# CAN_Test_Runner.net
KiCad netlist of a schematic drawn in Altium Designer
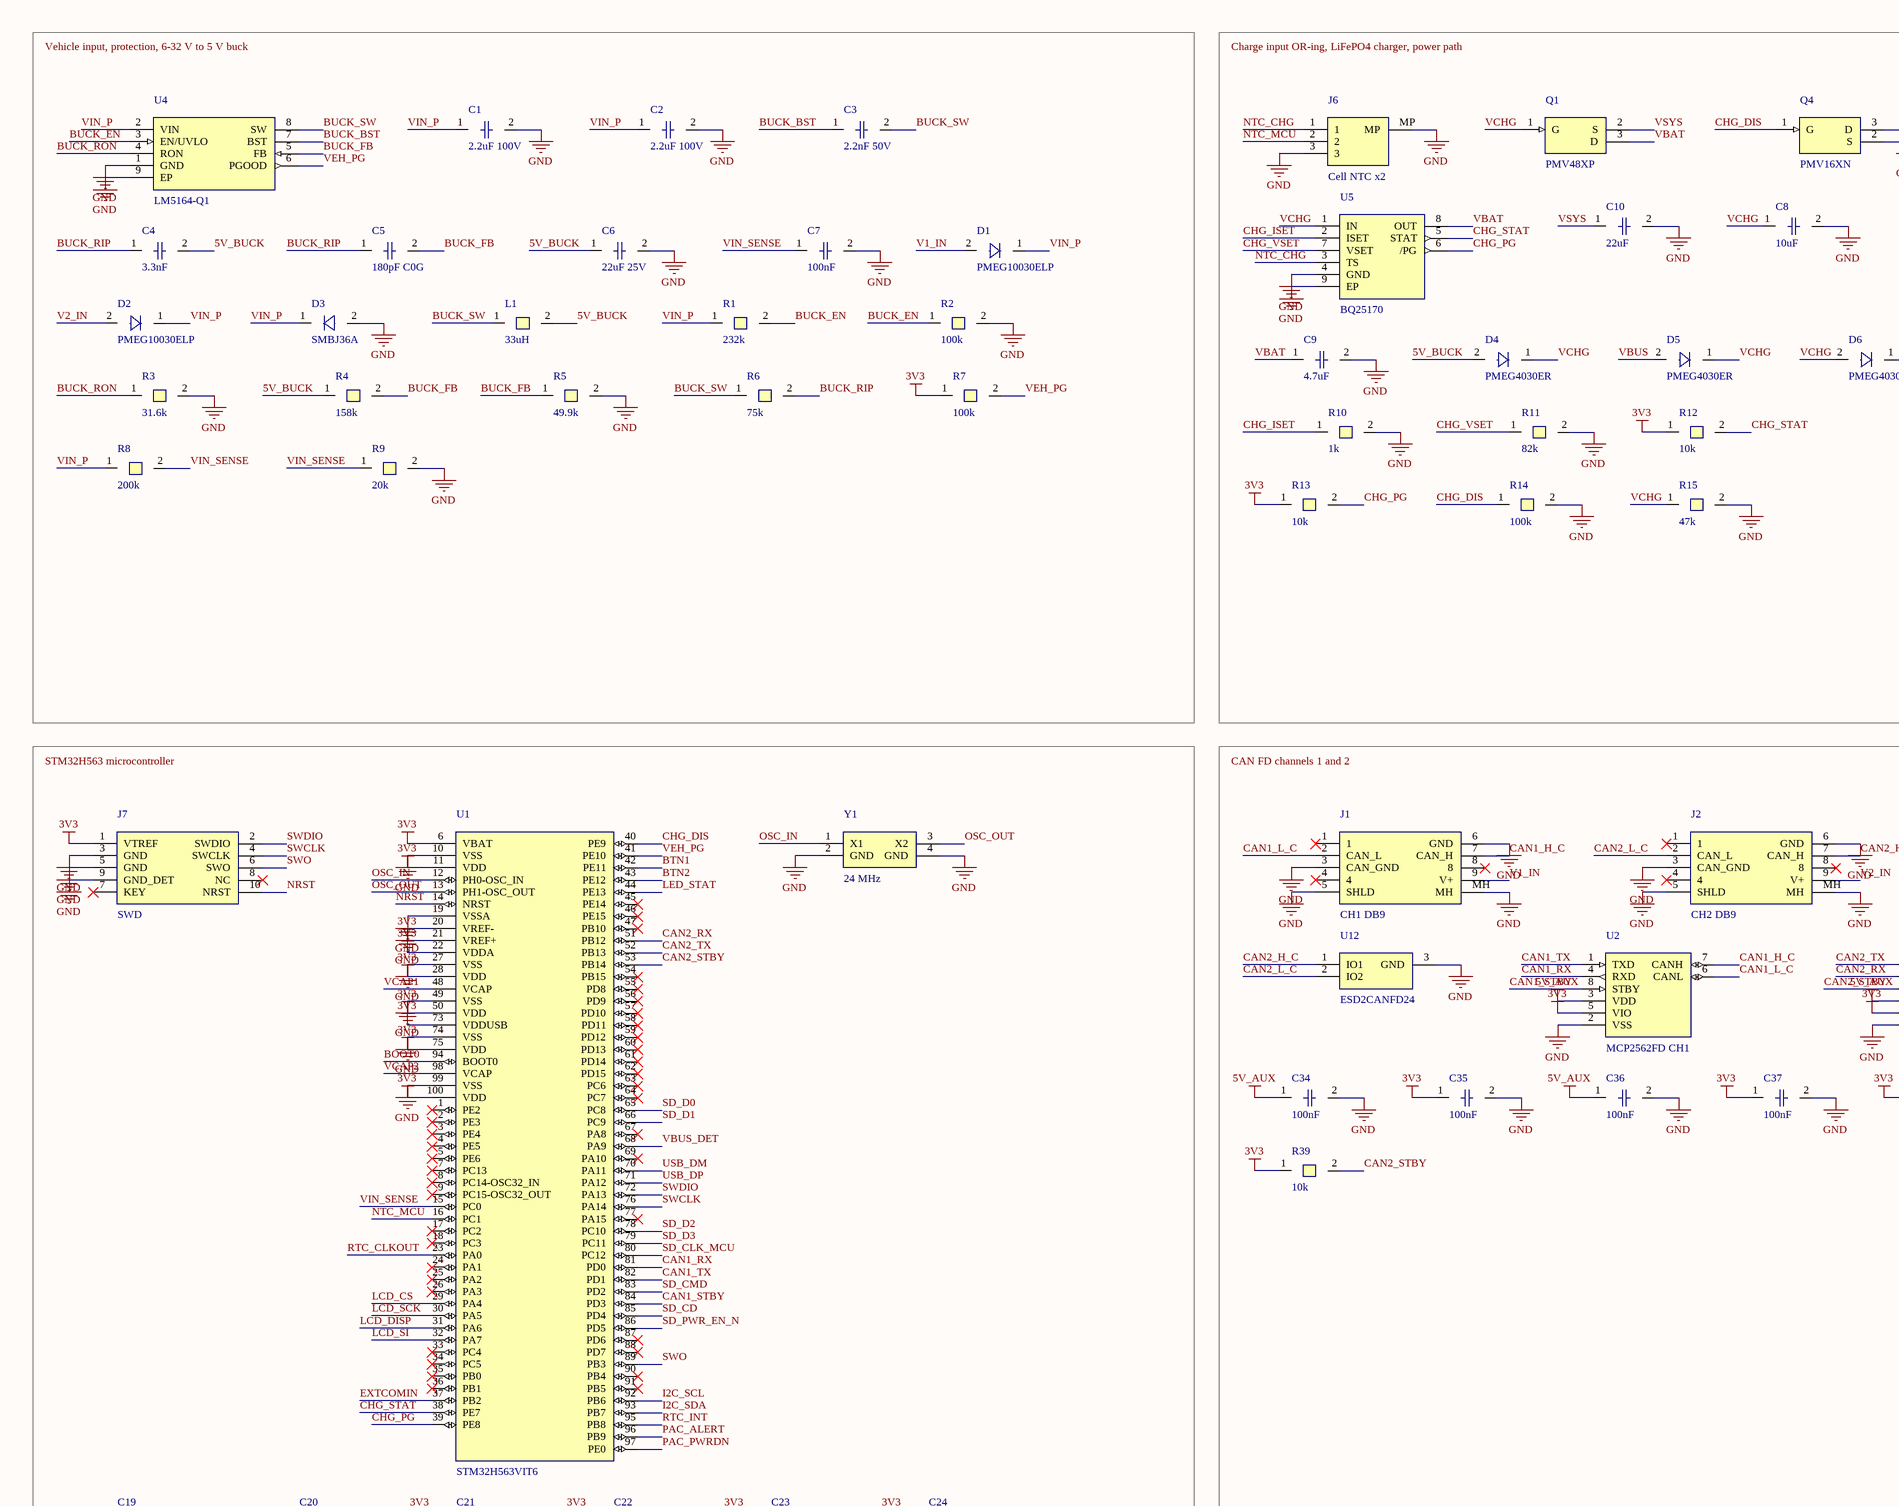
[diagram p0: CAN_Test_Runner.SchDoc, top left]
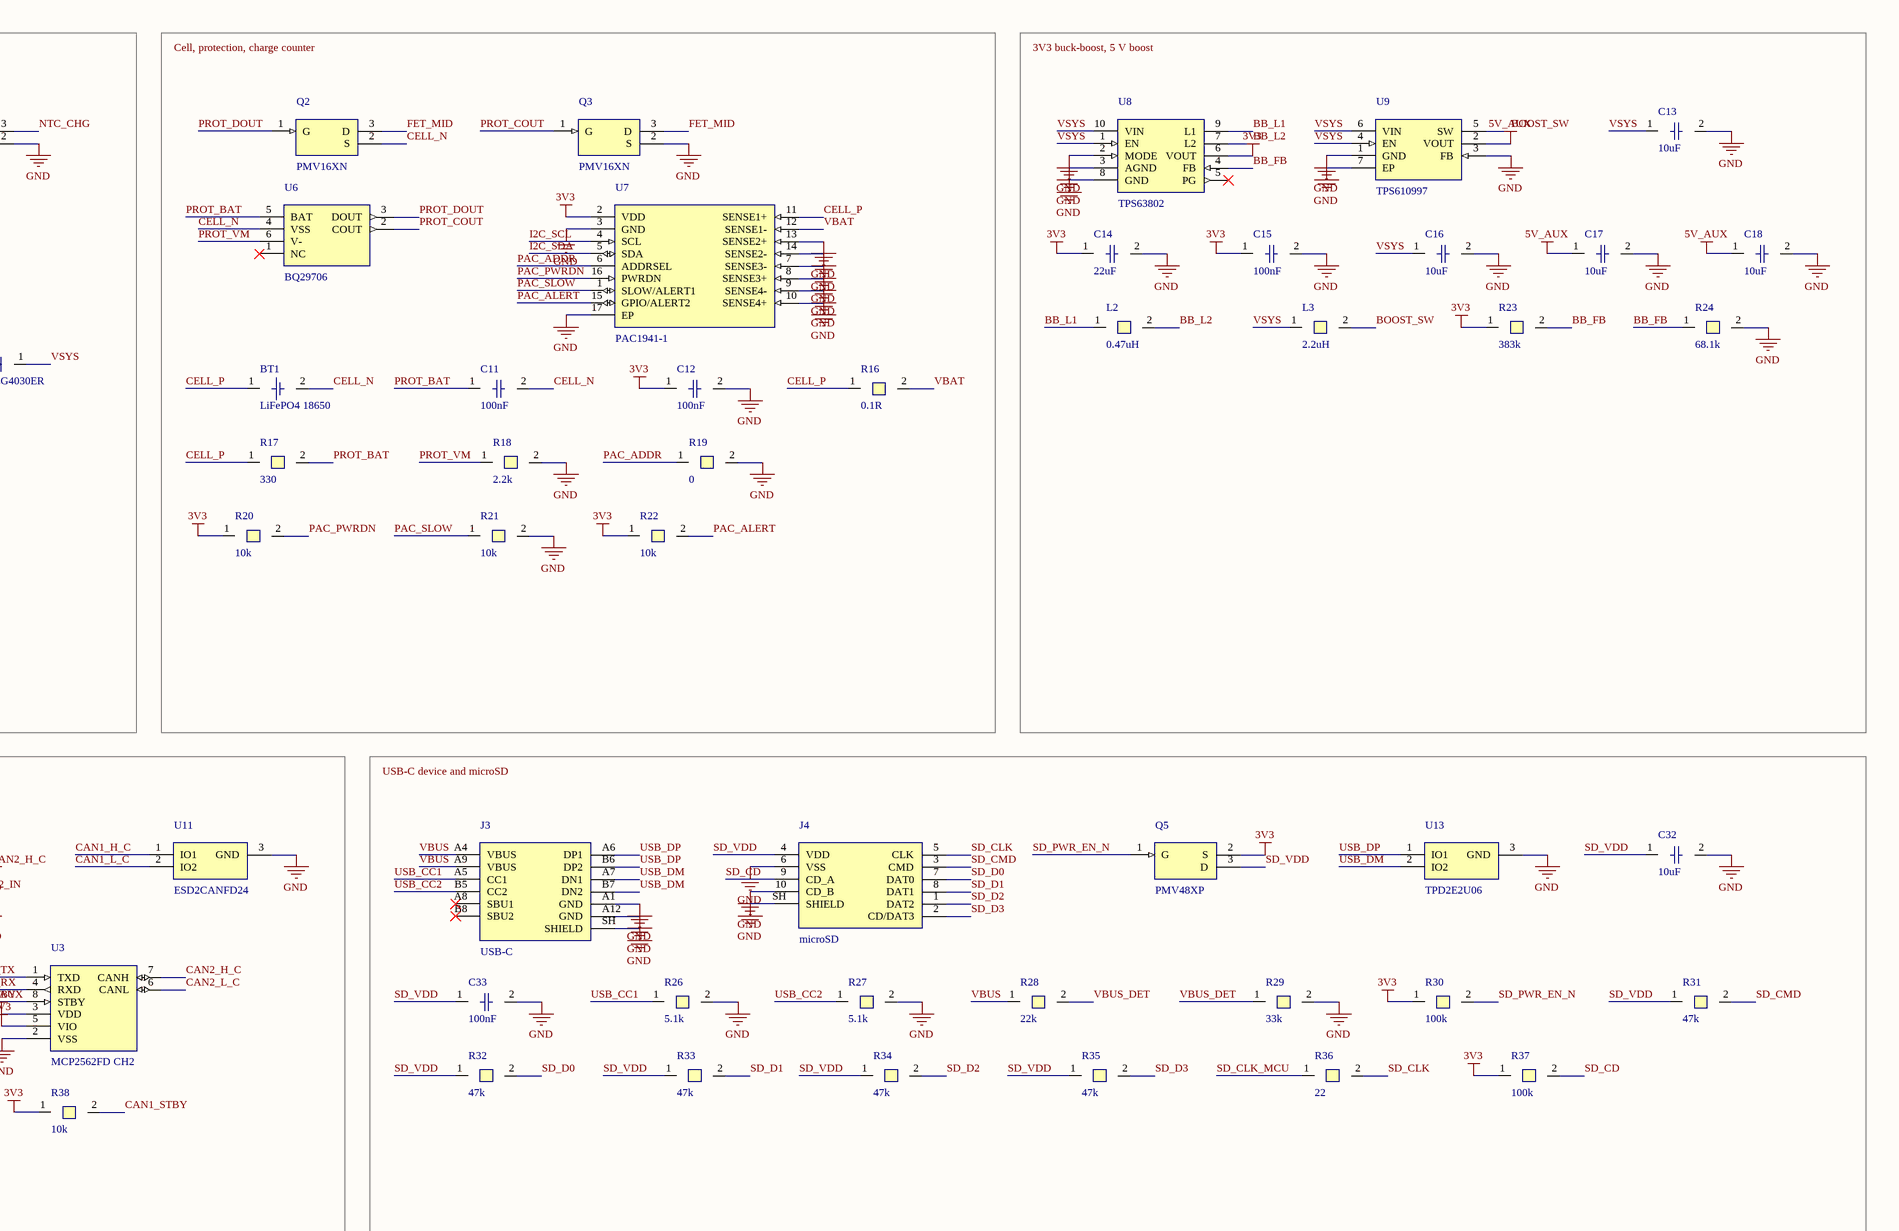
[diagram p1: CAN_Test_Runner.SchDoc, top right]
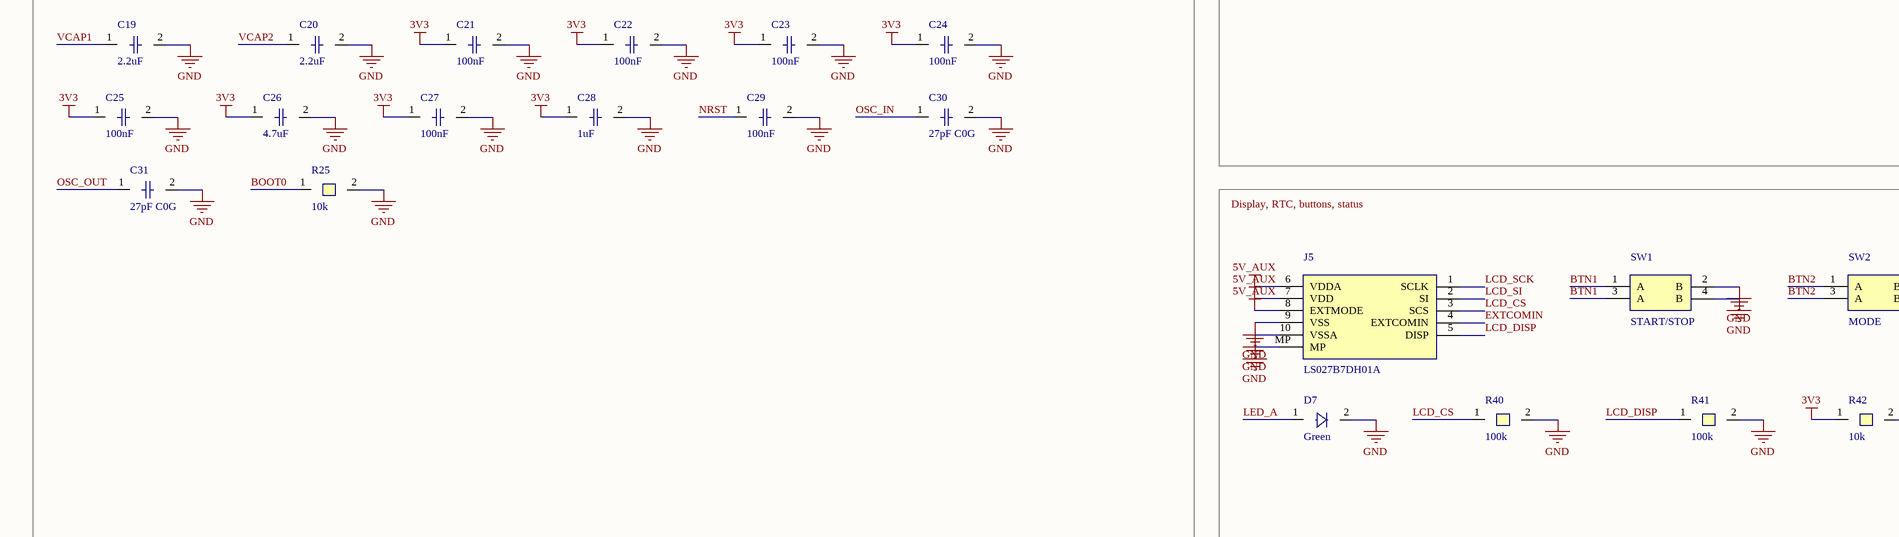
[diagram p2: CAN_Test_Runner.SchDoc, bottom left]
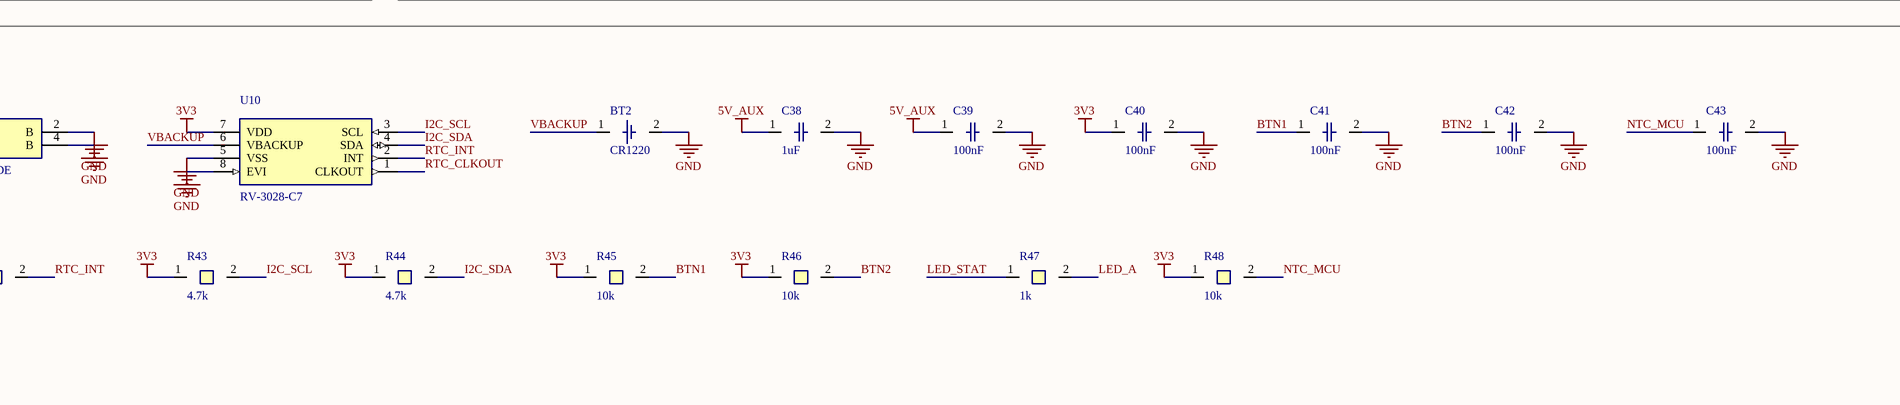
[diagram p3: CAN_Test_Runner.SchDoc, bottom right]

(export (version "E")
  (design (tool "Eeschema 10.0.6"))
  (components
    (comp (ref "BT1")
      (value "LiFePO4 18650")
      (footprint "BATT_KEYSTONE_1042_18650")
      (description "18650 cell holder")
      (fields (field (name "MPN") "Keystone 1042"))
      (libsource (lib "*") (part "BATT_18650"))
    )
    (comp (ref "BT2")
      (value "CR1220")
      (footprint "BATT_KEYSTONE_3000_12MM")
      (description "Coin cell retainer")
      (fields (field (name "MPN") "Keystone 3000"))
      (libsource (lib "*") (part "BATT_COIN"))
    )
    (comp (ref "C1")
      (value "2.2uF 100V")
      (footprint "C1210")
      (description "Capacitor, non-polarised")
      (fields (field (name "MPN") "generic 1210 X7R/C0G"))
      (libsource (lib "*") (part "CAP"))
    )
    (comp (ref "C2")
      (value "2.2uF 100V")
      (footprint "C1210")
      (description "Capacitor, non-polarised")
      (fields (field (name "MPN") "generic 1210 X7R/C0G"))
      (libsource (lib "*") (part "CAP"))
    )
    (comp (ref "C3")
      (value "2.2nF 50V")
      (footprint "C0603")
      (description "Capacitor, non-polarised")
      (fields (field (name "MPN") "generic 0603 X7R/C0G"))
      (libsource (lib "*") (part "CAP"))
    )
    (comp (ref "C4")
      (value "3.3nF")
      (footprint "C0603")
      (description "Capacitor, non-polarised")
      (fields (field (name "MPN") "generic 0603 X7R/C0G"))
      (libsource (lib "*") (part "CAP"))
    )
    (comp (ref "C5")
      (value "180pF C0G")
      (footprint "C0603")
      (description "Capacitor, non-polarised")
      (fields (field (name "MPN") "generic 0603 X7R/C0G"))
      (libsource (lib "*") (part "CAP"))
    )
    (comp (ref "C6")
      (value "22uF 25V")
      (footprint "C1210")
      (description "Capacitor, non-polarised")
      (fields (field (name "MPN") "generic 1210 X7R/C0G"))
      (libsource (lib "*") (part "CAP"))
    )
    (comp (ref "C7")
      (value "100nF")
      (footprint "C0603")
      (description "Capacitor, non-polarised")
      (fields (field (name "MPN") "generic 0603 X7R/C0G"))
      (libsource (lib "*") (part "CAP"))
    )
    (comp (ref "C8")
      (value "10uF")
      (footprint "C0805")
      (description "Capacitor, non-polarised")
      (fields (field (name "MPN") "generic 0805 X7R/C0G"))
      (libsource (lib "*") (part "CAP"))
    )
    (comp (ref "C9")
      (value "4.7uF")
      (footprint "C0805")
      (description "Capacitor, non-polarised")
      (fields (field (name "MPN") "generic 0805 X7R/C0G"))
      (libsource (lib "*") (part "CAP"))
    )
    (comp (ref "C10")
      (value "22uF")
      (footprint "C1210")
      (description "Capacitor, non-polarised")
      (fields (field (name "MPN") "generic 1210 X7R/C0G"))
      (libsource (lib "*") (part "CAP"))
    )
    (comp (ref "C11")
      (value "100nF")
      (footprint "C0603")
      (description "Capacitor, non-polarised")
      (fields (field (name "MPN") "generic 0603 X7R/C0G"))
      (libsource (lib "*") (part "CAP"))
    )
    (comp (ref "C12")
      (value "100nF")
      (footprint "C0603")
      (description "Capacitor, non-polarised")
      (fields (field (name "MPN") "generic 0603 X7R/C0G"))
      (libsource (lib "*") (part "CAP"))
    )
    (comp (ref "C13")
      (value "10uF")
      (footprint "C0805")
      (description "Capacitor, non-polarised")
      (fields (field (name "MPN") "generic 0805 X7R/C0G"))
      (libsource (lib "*") (part "CAP"))
    )
    (comp (ref "C14")
      (value "22uF")
      (footprint "C0805")
      (description "Capacitor, non-polarised")
      (fields (field (name "MPN") "generic 0805 X7R/C0G"))
      (libsource (lib "*") (part "CAP"))
    )
    (comp (ref "C15")
      (value "100nF")
      (footprint "C0603")
      (description "Capacitor, non-polarised")
      (fields (field (name "MPN") "generic 0603 X7R/C0G"))
      (libsource (lib "*") (part "CAP"))
    )
    (comp (ref "C16")
      (value "10uF")
      (footprint "C0805")
      (description "Capacitor, non-polarised")
      (fields (field (name "MPN") "generic 0805 X7R/C0G"))
      (libsource (lib "*") (part "CAP"))
    )
    (comp (ref "C17")
      (value "10uF")
      (footprint "C0805")
      (description "Capacitor, non-polarised")
      (fields (field (name "MPN") "generic 0805 X7R/C0G"))
      (libsource (lib "*") (part "CAP"))
    )
    (comp (ref "C18")
      (value "10uF")
      (footprint "C0805")
      (description "Capacitor, non-polarised")
      (fields (field (name "MPN") "generic 0805 X7R/C0G"))
      (libsource (lib "*") (part "CAP"))
    )
    (comp (ref "C19")
      (value "2.2uF")
      (footprint "C0603")
      (description "Capacitor, non-polarised")
      (fields (field (name "MPN") "generic 0603 X7R/C0G"))
      (libsource (lib "*") (part "CAP"))
    )
    (comp (ref "C20")
      (value "2.2uF")
      (footprint "C0603")
      (description "Capacitor, non-polarised")
      (fields (field (name "MPN") "generic 0603 X7R/C0G"))
      (libsource (lib "*") (part "CAP"))
    )
    (comp (ref "C21")
      (value "100nF")
      (footprint "C0603")
      (description "Capacitor, non-polarised")
      (fields (field (name "MPN") "generic 0603 X7R/C0G"))
      (libsource (lib "*") (part "CAP"))
    )
    (comp (ref "C22")
      (value "100nF")
      (footprint "C0603")
      (description "Capacitor, non-polarised")
      (fields (field (name "MPN") "generic 0603 X7R/C0G"))
      (libsource (lib "*") (part "CAP"))
    )
    (comp (ref "C23")
      (value "100nF")
      (footprint "C0603")
      (description "Capacitor, non-polarised")
      (fields (field (name "MPN") "generic 0603 X7R/C0G"))
      (libsource (lib "*") (part "CAP"))
    )
    (comp (ref "C24")
      (value "100nF")
      (footprint "C0603")
      (description "Capacitor, non-polarised")
      (fields (field (name "MPN") "generic 0603 X7R/C0G"))
      (libsource (lib "*") (part "CAP"))
    )
    (comp (ref "C25")
      (value "100nF")
      (footprint "C0603")
      (description "Capacitor, non-polarised")
      (fields (field (name "MPN") "generic 0603 X7R/C0G"))
      (libsource (lib "*") (part "CAP"))
    )
    (comp (ref "C26")
      (value "4.7uF")
      (footprint "C0805")
      (description "Capacitor, non-polarised")
      (fields (field (name "MPN") "generic 0805 X7R/C0G"))
      (libsource (lib "*") (part "CAP"))
    )
    (comp (ref "C27")
      (value "100nF")
      (footprint "C0603")
      (description "Capacitor, non-polarised")
      (fields (field (name "MPN") "generic 0603 X7R/C0G"))
      (libsource (lib "*") (part "CAP"))
    )
    (comp (ref "C28")
      (value "1uF")
      (footprint "C0603")
      (description "Capacitor, non-polarised")
      (fields (field (name "MPN") "generic 0603 X7R/C0G"))
      (libsource (lib "*") (part "CAP"))
    )
    (comp (ref "C29")
      (value "100nF")
      (footprint "C0603")
      (description "Capacitor, non-polarised")
      (fields (field (name "MPN") "generic 0603 X7R/C0G"))
      (libsource (lib "*") (part "CAP"))
    )
    (comp (ref "C30")
      (value "27pF C0G")
      (footprint "C0603")
      (description "Capacitor, non-polarised")
      (fields (field (name "MPN") "generic 0603 X7R/C0G"))
      (libsource (lib "*") (part "CAP"))
    )
    (comp (ref "C31")
      (value "27pF C0G")
      (footprint "C0603")
      (description "Capacitor, non-polarised")
      (fields (field (name "MPN") "generic 0603 X7R/C0G"))
      (libsource (lib "*") (part "CAP"))
    )
    (comp (ref "C32")
      (value "10uF")
      (footprint "C0805")
      (description "Capacitor, non-polarised")
      (fields (field (name "MPN") "generic 0805 X7R/C0G"))
      (libsource (lib "*") (part "CAP"))
    )
    (comp (ref "C33")
      (value "100nF")
      (footprint "C0603")
      (description "Capacitor, non-polarised")
      (fields (field (name "MPN") "generic 0603 X7R/C0G"))
      (libsource (lib "*") (part "CAP"))
    )
    (comp (ref "C34")
      (value "100nF")
      (footprint "C0603")
      (description "Capacitor, non-polarised")
      (fields (field (name "MPN") "generic 0603 X7R/C0G"))
      (libsource (lib "*") (part "CAP"))
    )
    (comp (ref "C35")
      (value "100nF")
      (footprint "C0603")
      (description "Capacitor, non-polarised")
      (fields (field (name "MPN") "generic 0603 X7R/C0G"))
      (libsource (lib "*") (part "CAP"))
    )
    (comp (ref "C36")
      (value "100nF")
      (footprint "C0603")
      (description "Capacitor, non-polarised")
      (fields (field (name "MPN") "generic 0603 X7R/C0G"))
      (libsource (lib "*") (part "CAP"))
    )
    (comp (ref "C37")
      (value "100nF")
      (footprint "C0603")
      (description "Capacitor, non-polarised")
      (fields (field (name "MPN") "generic 0603 X7R/C0G"))
      (libsource (lib "*") (part "CAP"))
    )
    (comp (ref "C38")
      (value "1uF")
      (footprint "C0603")
      (description "Capacitor, non-polarised")
      (fields (field (name "MPN") "generic 0603 X7R/C0G"))
      (libsource (lib "*") (part "CAP"))
    )
    (comp (ref "C39")
      (value "100nF")
      (footprint "C0603")
      (description "Capacitor, non-polarised")
      (fields (field (name "MPN") "generic 0603 X7R/C0G"))
      (libsource (lib "*") (part "CAP"))
    )
    (comp (ref "C40")
      (value "100nF")
      (footprint "C0603")
      (description "Capacitor, non-polarised")
      (fields (field (name "MPN") "generic 0603 X7R/C0G"))
      (libsource (lib "*") (part "CAP"))
    )
    (comp (ref "C41")
      (value "100nF")
      (footprint "C0603")
      (description "Capacitor, non-polarised")
      (fields (field (name "MPN") "generic 0603 X7R/C0G"))
      (libsource (lib "*") (part "CAP"))
    )
    (comp (ref "C42")
      (value "100nF")
      (footprint "C0603")
      (description "Capacitor, non-polarised")
      (fields (field (name "MPN") "generic 0603 X7R/C0G"))
      (libsource (lib "*") (part "CAP"))
    )
    (comp (ref "C43")
      (value "100nF")
      (footprint "C0603")
      (description "Capacitor, non-polarised")
      (fields (field (name "MPN") "generic 0603 X7R/C0G"))
      (libsource (lib "*") (part "CAP"))
    )
    (comp (ref "D1")
      (value "PMEG10030ELP")
      (footprint "SOD128")
      (description "Schottky diode (pad 1 = cathode)")
      (fields (field (name "MPN") "Nexperia PMEG10030ELPX"))
      (libsource (lib "*") (part "DIODE_SCHOTTKY"))
    )
    (comp (ref "D2")
      (value "PMEG10030ELP")
      (footprint "SOD128")
      (description "Schottky diode (pad 1 = cathode)")
      (fields (field (name "MPN") "Nexperia PMEG10030ELPX"))
      (libsource (lib "*") (part "DIODE_SCHOTTKY"))
    )
    (comp (ref "D3")
      (value "SMBJ36A")
      (footprint "SMB")
      (description "Unidirectional TVS (pad 1 = cathode)")
      (fields (field (name "MPN") "Bourns SMBJ36A"))
      (libsource (lib "*") (part "TVS_UNI"))
    )
    (comp (ref "D4")
      (value "PMEG4030ER")
      (footprint "SOD123W")
      (description "Schottky diode (pad 1 = cathode)")
      (fields (field (name "MPN") "Nexperia PMEG4030ERX"))
      (libsource (lib "*") (part "DIODE_SCHOTTKY"))
    )
    (comp (ref "D5")
      (value "PMEG4030ER")
      (footprint "SOD123W")
      (description "Schottky diode (pad 1 = cathode)")
      (fields (field (name "MPN") "Nexperia PMEG4030ERX"))
      (libsource (lib "*") (part "DIODE_SCHOTTKY"))
    )
    (comp (ref "D6")
      (value "PMEG4030ER")
      (footprint "SOD123W")
      (description "Schottky diode (pad 1 = cathode)")
      (fields (field (name "MPN") "Nexperia PMEG4030ERX"))
      (libsource (lib "*") (part "DIODE_SCHOTTKY"))
    )
    (comp (ref "D7")
      (value "Green")
      (footprint "LED0603")
      (description "LED")
      (fields (field (name "MPN") "generic 0603 green LED"))
      (libsource (lib "*") (part "LED"))
    )
    (comp (ref "J1")
      (value "CH1 DB9")
      (footprint "DSUB-9_M_WR-DSUB_618009231221")
      (description "DB9 male, CiA 303-1: 2 CAN_L, 3 CAN_GND, 5 SHLD, 6 GND, 7 CAN_H, 9 V+")
      (fields (field (name "MPN") "Wurth 618009231221"))
      (libsource (lib "*") (part "DB9_M"))
    )
    (comp (ref "J2")
      (value "CH2 DB9")
      (footprint "DSUB-9_M_WR-DSUB_618009231221")
      (description "DB9 male, CiA 303-1: 2 CAN_L, 3 CAN_GND, 5 SHLD, 6 GND, 7 CAN_H, 9 V+")
      (fields (field (name "MPN") "Wurth 618009231221"))
      (libsource (lib "*") (part "DB9_M"))
    )
    (comp (ref "J3")
      (value "USB-C")
      (footprint "USB-C_GCT_USB4105")
      (description "USB-C 2.0 receptacle")
      (fields (field (name "MPN") "GCT USB4105-GF-A"))
      (libsource (lib "*") (part "USB_C"))
    )
    (comp (ref "J4")
      (value "microSD")
      (footprint "MICROSD_HIROSE_DM3AT")
      (description "microSD push-push with card-detect switch (9/10)")
      (fields (field (name "MPN") "Hirose DM3AT-SF-PEJM5"))
      (libsource (lib "*") (part "MICROSD"))
    )
    (comp (ref "J5")
      (value "LS027B7DH01A")
      (footprint "FPC_10P_0.5_WR-FPC_687110149022")
      (description "10-pin 0.5 mm FPC, Sharp LS027B7DH01A pin order")
      (fields (field (name "MPN") "Wurth 687110149022"))
      (libsource (lib "*") (part "FPC10_LCD"))
    )
    (comp (ref "J6")
      (value "Cell NTC x2")
      (footprint "JST_PH_S3B-PH-SM4-TB")
      (description "3-pin connector")
      (fields (field (name "MPN") "JST S3B-PH-SM4-TB"))
      (libsource (lib "*") (part "CONN3"))
    )
    (comp (ref "J7")
      (value "SWD")
      (footprint "TAG-CONNECT_TC2050-IDC-NL")
      (description "Tag-Connect TC2050, Cortex 10-pin SWD")
      (fields (field (name "MPN") "Tag-Connect TC2050-IDC-NL (footprint only)"))
      (libsource (lib "*") (part "SWD_TC2050"))
    )
    (comp (ref "L1")
      (value "33uH")
      (footprint "L_WE-LQS-6045")
      (description "Inductor")
      (fields (field (name "MPN") "Wurth 74404064330"))
      (libsource (lib "*") (part "IND"))
    )
    (comp (ref "L2")
      (value "0.47uH")
      (footprint "L_WE-MAPI-2016")
      (description "Inductor")
      (fields (field (name "MPN") "Wurth 744383430047"))
      (libsource (lib "*") (part "IND"))
    )
    (comp (ref "L3")
      (value "2.2uH")
      (footprint "L_WE-LQS-2520")
      (description "Inductor")
      (fields (field (name "MPN") "Wurth 74404024022"))
      (libsource (lib "*") (part "IND"))
    )
    (comp (ref "Q1")
      (value "PMV48XP")
      (footprint "SOT-23-3")
      (description "P-channel MOSFET, SOT-23")
      (fields (field (name "MPN") "Nexperia PMV48XP"))
      (libsource (lib "*") (part "PMOS"))
    )
    (comp (ref "Q2")
      (value "PMV16XN")
      (footprint "SOT-23-3")
      (description "N-channel MOSFET, SOT-23")
      (fields (field (name "MPN") "Nexperia PMV16XN"))
      (libsource (lib "*") (part "NMOS"))
    )
    (comp (ref "Q3")
      (value "PMV16XN")
      (footprint "SOT-23-3")
      (description "N-channel MOSFET, SOT-23")
      (fields (field (name "MPN") "Nexperia PMV16XN"))
      (libsource (lib "*") (part "NMOS"))
    )
    (comp (ref "Q4")
      (value "PMV16XN")
      (footprint "SOT-23-3")
      (description "N-channel MOSFET, SOT-23")
      (fields (field (name "MPN") "Nexperia PMV16XN"))
      (libsource (lib "*") (part "NMOS"))
    )
    (comp (ref "Q5")
      (value "PMV48XP")
      (footprint "SOT-23-3")
      (description "P-channel MOSFET, SOT-23")
      (fields (field (name "MPN") "Nexperia PMV48XP"))
      (libsource (lib "*") (part "PMOS"))
    )
    (comp (ref "R1")
      (value "232k")
      (footprint "R0603")
      (description "Resistor")
      (fields (field (name "MPN") "generic 0603 1%"))
      (libsource (lib "*") (part "RES"))
    )
    (comp (ref "R2")
      (value "100k")
      (footprint "R0603")
      (description "Resistor")
      (fields (field (name "MPN") "generic 0603 1%"))
      (libsource (lib "*") (part "RES"))
    )
    (comp (ref "R3")
      (value "31.6k")
      (footprint "R0603")
      (description "Resistor")
      (fields (field (name "MPN") "generic 0603 1%"))
      (libsource (lib "*") (part "RES"))
    )
    (comp (ref "R4")
      (value "158k")
      (footprint "R0603")
      (description "Resistor")
      (fields (field (name "MPN") "generic 0603 1%"))
      (libsource (lib "*") (part "RES"))
    )
    (comp (ref "R5")
      (value "49.9k")
      (footprint "R0603")
      (description "Resistor")
      (fields (field (name "MPN") "generic 0603 1%"))
      (libsource (lib "*") (part "RES"))
    )
    (comp (ref "R6")
      (value "75k")
      (footprint "R0603")
      (description "Resistor")
      (fields (field (name "MPN") "generic 0603 1%"))
      (libsource (lib "*") (part "RES"))
    )
    (comp (ref "R7")
      (value "100k")
      (footprint "R0603")
      (description "Resistor")
      (fields (field (name "MPN") "generic 0603 1%"))
      (libsource (lib "*") (part "RES"))
    )
    (comp (ref "R8")
      (value "200k")
      (footprint "R0603")
      (description "Resistor")
      (fields (field (name "MPN") "generic 0603 1%"))
      (libsource (lib "*") (part "RES"))
    )
    (comp (ref "R9")
      (value "20k")
      (footprint "R0603")
      (description "Resistor")
      (fields (field (name "MPN") "generic 0603 1%"))
      (libsource (lib "*") (part "RES"))
    )
    (comp (ref "R10")
      (value "1k")
      (footprint "R0603")
      (description "Resistor")
      (fields (field (name "MPN") "generic 0603 1%"))
      (libsource (lib "*") (part "RES"))
    )
    (comp (ref "R11")
      (value "82k")
      (footprint "R0603")
      (description "Resistor")
      (fields (field (name "MPN") "generic 0603 1%"))
      (libsource (lib "*") (part "RES"))
    )
    (comp (ref "R12")
      (value "10k")
      (footprint "R0603")
      (description "Resistor")
      (fields (field (name "MPN") "generic 0603 1%"))
      (libsource (lib "*") (part "RES"))
    )
    (comp (ref "R13")
      (value "10k")
      (footprint "R0603")
      (description "Resistor")
      (fields (field (name "MPN") "generic 0603 1%"))
      (libsource (lib "*") (part "RES"))
    )
    (comp (ref "R14")
      (value "100k")
      (footprint "R0603")
      (description "Resistor")
      (fields (field (name "MPN") "generic 0603 1%"))
      (libsource (lib "*") (part "RES"))
    )
    (comp (ref "R15")
      (value "47k")
      (footprint "R0603")
      (description "Resistor")
      (fields (field (name "MPN") "generic 0603 1%"))
      (libsource (lib "*") (part "RES"))
    )
    (comp (ref "R16")
      (value "0.1R")
      (footprint "R0805")
      (description "Resistor")
      (fields (field (name "MPN") "generic 0805 1%"))
      (libsource (lib "*") (part "RES"))
    )
    (comp (ref "R17")
      (value "330")
      (footprint "R0603")
      (description "Resistor")
      (fields (field (name "MPN") "generic 0603 1%"))
      (libsource (lib "*") (part "RES"))
    )
    (comp (ref "R18")
      (value "2.2k")
      (footprint "R0603")
      (description "Resistor")
      (fields (field (name "MPN") "generic 0603 1%"))
      (libsource (lib "*") (part "RES"))
    )
    (comp (ref "R19")
      (value "0")
      (footprint "R0603")
      (description "Resistor")
      (fields (field (name "MPN") "generic 0603 1%"))
      (libsource (lib "*") (part "RES"))
    )
    (comp (ref "R20")
      (value "10k")
      (footprint "R0603")
      (description "Resistor")
      (fields (field (name "MPN") "generic 0603 1%"))
      (libsource (lib "*") (part "RES"))
    )
    (comp (ref "R21")
      (value "10k")
      (footprint "R0603")
      (description "Resistor")
      (fields (field (name "MPN") "generic 0603 1%"))
      (libsource (lib "*") (part "RES"))
    )
    (comp (ref "R22")
      (value "10k")
      (footprint "R0603")
      (description "Resistor")
      (fields (field (name "MPN") "generic 0603 1%"))
      (libsource (lib "*") (part "RES"))
    )
    (comp (ref "R23")
      (value "383k")
      (footprint "R0603")
      (description "Resistor")
      (fields (field (name "MPN") "generic 0603 1%"))
      (libsource (lib "*") (part "RES"))
    )
    (comp (ref "R24")
      (value "68.1k")
      (footprint "R0603")
      (description "Resistor")
      (fields (field (name "MPN") "generic 0603 1%"))
      (libsource (lib "*") (part "RES"))
    )
    (comp (ref "R25")
      (value "10k")
      (footprint "R0603")
      (description "Resistor")
      (fields (field (name "MPN") "generic 0603 1%"))
      (libsource (lib "*") (part "RES"))
    )
    (comp (ref "R26")
      (value "5.1k")
      (footprint "R0603")
      (description "Resistor")
      (fields (field (name "MPN") "generic 0603 1%"))
      (libsource (lib "*") (part "RES"))
    )
    (comp (ref "R27")
      (value "5.1k")
      (footprint "R0603")
      (description "Resistor")
      (fields (field (name "MPN") "generic 0603 1%"))
      (libsource (lib "*") (part "RES"))
    )
    (comp (ref "R28")
      (value "22k")
      (footprint "R0603")
      (description "Resistor")
      (fields (field (name "MPN") "generic 0603 1%"))
      (libsource (lib "*") (part "RES"))
    )
    (comp (ref "R29")
      (value "33k")
      (footprint "R0603")
      (description "Resistor")
      (fields (field (name "MPN") "generic 0603 1%"))
      (libsource (lib "*") (part "RES"))
    )
    (comp (ref "R30")
      (value "100k")
      (footprint "R0603")
      (description "Resistor")
      (fields (field (name "MPN") "generic 0603 1%"))
      (libsource (lib "*") (part "RES"))
    )
    (comp (ref "R31")
      (value "47k")
      (footprint "R0603")
      (description "Resistor")
      (fields (field (name "MPN") "generic 0603 1%"))
      (libsource (lib "*") (part "RES"))
    )
    (comp (ref "R32")
      (value "47k")
      (footprint "R0603")
      (description "Resistor")
      (fields (field (name "MPN") "generic 0603 1%"))
      (libsource (lib "*") (part "RES"))
    )
    (comp (ref "R33")
      (value "47k")
      (footprint "R0603")
      (description "Resistor")
      (fields (field (name "MPN") "generic 0603 1%"))
      (libsource (lib "*") (part "RES"))
    )
    (comp (ref "R34")
      (value "47k")
      (footprint "R0603")
      (description "Resistor")
      (fields (field (name "MPN") "generic 0603 1%"))
      (libsource (lib "*") (part "RES"))
    )
    (comp (ref "R35")
      (value "47k")
      (footprint "R0603")
      (description "Resistor")
      (fields (field (name "MPN") "generic 0603 1%"))
      (libsource (lib "*") (part "RES"))
    )
    (comp (ref "R36")
      (value "22")
      (footprint "R0603")
      (description "Resistor")
      (fields (field (name "MPN") "generic 0603 1%"))
      (libsource (lib "*") (part "RES"))
    )
    (comp (ref "R37")
      (value "100k")
      (footprint "R0603")
      (description "Resistor")
      (fields (field (name "MPN") "generic 0603 1%"))
      (libsource (lib "*") (part "RES"))
    )
    (comp (ref "R38")
      (value "10k")
      (footprint "R0603")
      (description "Resistor")
      (fields (field (name "MPN") "generic 0603 1%"))
      (libsource (lib "*") (part "RES"))
    )
    (comp (ref "R39")
      (value "10k")
      (footprint "R0603")
      (description "Resistor")
      (fields (field (name "MPN") "generic 0603 1%"))
      (libsource (lib "*") (part "RES"))
    )
    (comp (ref "R40")
      (value "100k")
      (footprint "R0603")
      (description "Resistor")
      (fields (field (name "MPN") "generic 0603 1%"))
      (libsource (lib "*") (part "RES"))
    )
    (comp (ref "R41")
      (value "100k")
      (footprint "R0603")
      (description "Resistor")
      (fields (field (name "MPN") "generic 0603 1%"))
      (libsource (lib "*") (part "RES"))
    )
    (comp (ref "R42")
      (value "10k")
      (footprint "R0603")
      (description "Resistor")
      (fields (field (name "MPN") "generic 0603 1%"))
      (libsource (lib "*") (part "RES"))
    )
    (comp (ref "R43")
      (value "4.7k")
      (footprint "R0603")
      (description "Resistor")
      (fields (field (name "MPN") "generic 0603 1%"))
      (libsource (lib "*") (part "RES"))
    )
    (comp (ref "R44")
      (value "4.7k")
      (footprint "R0603")
      (description "Resistor")
      (fields (field (name "MPN") "generic 0603 1%"))
      (libsource (lib "*") (part "RES"))
    )
    (comp (ref "R45")
      (value "10k")
      (footprint "R0603")
      (description "Resistor")
      (fields (field (name "MPN") "generic 0603 1%"))
      (libsource (lib "*") (part "RES"))
    )
    (comp (ref "R46")
      (value "10k")
      (footprint "R0603")
      (description "Resistor")
      (fields (field (name "MPN") "generic 0603 1%"))
      (libsource (lib "*") (part "RES"))
    )
    (comp (ref "R47")
      (value "1k")
      (footprint "R0603")
      (description "Resistor")
      (fields (field (name "MPN") "generic 0603 1%"))
      (libsource (lib "*") (part "RES"))
    )
    (comp (ref "R48")
      (value "10k")
      (footprint "R0603")
      (description "Resistor")
      (fields (field (name "MPN") "generic 0603 1%"))
      (libsource (lib "*") (part "RES"))
    )
    (comp (ref "SW1")
      (value "START/STOP")
      (footprint "SW_WS-TASV_6x6")
      (description "Tactile switch, pads 1/3 and 2/4 common")
      (fields (field (name "MPN") "Wurth 430182050816"))
      (libsource (lib "*") (part "SW_4P"))
    )
    (comp (ref "SW2")
      (value "MODE")
      (footprint "SW_WS-TASV_6x6")
      (description "Tactile switch, pads 1/3 and 2/4 common")
      (fields (field (name "MPN") "Wurth 430182050816"))
      (libsource (lib "*") (part "SW_4P"))
    )
    (comp (ref "U1")
      (value "STM32H563VIT6")
      (footprint "LQFP-100_14x14")
      (description "STM32H563VIT6 Cortex-M33 250 MHz, 2 MB flash, 640 KB SRAM, LQFP-100")
      (fields (field (name "MPN") "ST STM32H563VIT6"))
      (libsource (lib "*") (part "STM32H563VIT6"))
    )
    (comp (ref "U2")
      (value "MCP2562FD CH1")
      (footprint "SOIC-8_150MIL")
      (description "CAN FD transceiver with VIO, SOIC-8")
      (fields (field (name "MPN") "Microchip MCP2562FD-E/SN"))
      (libsource (lib "*") (part "MCP2562FD"))
    )
    (comp (ref "U3")
      (value "MCP2562FD CH2")
      (footprint "SOIC-8_150MIL")
      (description "CAN FD transceiver with VIO, SOIC-8")
      (fields (field (name "MPN") "Microchip MCP2562FD-E/SN"))
      (libsource (lib "*") (part "MCP2562FD"))
    )
    (comp (ref "U4")
      (value "LM5164-Q1")
      (footprint "SOIC-8_DDA_PowerPAD")
      (description "LM5164-Q1 100 V 1 A synchronous buck, DDA PowerPAD")
      (fields (field (name "MPN") "TI LM5164QDDARQ1"))
      (libsource (lib "*") (part "LM5164"))
    )
    (comp (ref "U5")
      (value "BQ25170")
      (footprint "WSON-8_DSG")
      (description "BQ25170 800 mA linear charger, Li-ion / LiFePO4, WSON-8")
      (fields (field (name "MPN") "TI BQ25170DSGR"))
      (libsource (lib "*") (part "BQ25170"))
    )
    (comp (ref "U6")
      (value "BQ29706")
      (footprint "WSON-6_DSE")
      (description "BQ29706 single-cell protector, OVP 3.85 V / UVP 2.5 V, WSON-6")
      (fields (field (name "MPN") "TI BQ29706DSER"))
      (libsource (lib "*") (part "BQ2970"))
    )
    (comp (ref "U7")
      (value "PAC1941-1")
      (footprint "VQFN-16_3x3_4MX")
      (description "PAC1941-1 power monitor with charge accumulator, VQFN-16")
      (fields (field (name "MPN") "Microchip PAC1941T-1E/4MX"))
      (libsource (lib "*") (part "PAC1941"))
    )
    (comp (ref "U8")
      (value "TPS63802")
      (footprint "VSON-10_DLA")
      (description "TPS63802 2 A buck-boost, VSON-10")
      (fields (field (name "MPN") "TI TPS63802DLAR"))
      (libsource (lib "*") (part "TPS63802"))
    )
    (comp (ref "U9")
      (value "TPS610997")
      (footprint "WSON-6_DRV")
      (description "TPS610997 5.0 V boost, 1 uA Iq, WSON-6")
      (fields (field (name "MPN") "TI TPS610997DRVR"))
      (libsource (lib "*") (part "TPS61099"))
    )
    (comp (ref "U10")
      (value "RV-3028-C7")
      (footprint "RV-3028-C7")
      (description "RV-3028-C7 RTC module, 45 nA")
      (fields (field (name "MPN") "Micro Crystal RV-3028-C7 32.768kHz 1ppm-TA-QC"))
      (libsource (lib "*") (part "RV3028"))
    )
    (comp (ref "U11")
      (value "ESD2CANFD24")
      (footprint "SOT-23-3")
      (description "ESD2CANFD24-Q1 CAN FD ESD protection, SOT-23")
      (fields (field (name "MPN") "TI ESD2CANFD24DBZRQ1"))
      (libsource (lib "*") (part "ESD_CAN"))
    )
    (comp (ref "U12")
      (value "ESD2CANFD24")
      (footprint "SOT-23-3")
      (description "ESD2CANFD24-Q1 CAN FD ESD protection, SOT-23")
      (fields (field (name "MPN") "TI ESD2CANFD24DBZRQ1"))
      (libsource (lib "*") (part "ESD_CAN"))
    )
    (comp (ref "U13")
      (value "TPD2E2U06")
      (footprint "SC-70-3")
      (description "TPD2E2U06 2-channel ESD, SC-70")
      (fields (field (name "MPN") "TI TPD2E2U06DCKR"))
      (libsource (lib "*") (part "ESD_2CH"))
    )
    (comp (ref "Y1")
      (value "24 MHz")
      (footprint "XTAL_3225_4P")
      (description "Crystal, 4-pad package, pads 2 and 4 = case")
      (fields (field (name "MPN") "Abracon ABM8-24.000MHZ-B2-T"))
      (libsource (lib "*") (part "XTAL_4P"))
    )
  )
  (nets
    (net (code "1") (name "/5V_BUCK") (class "Default")
      (node (ref "C4") (pin "2") (pinfunction "2_2") (pintype "passive"))
      (node (ref "C6") (pin "1") (pinfunction "1_1") (pintype "passive"))
      (node (ref "D4") (pin "2") (pinfunction "A_2") (pintype "passive"))
      (node (ref "L1") (pin "2") (pinfunction "2_2") (pintype "passive"))
      (node (ref "R4") (pin "1") (pinfunction "1_1") (pintype "passive"))
    )
    (net (code "2") (name "/BB_FB") (class "Default")
      (node (ref "R23") (pin "2") (pinfunction "2_2") (pintype "passive"))
      (node (ref "R24") (pin "1") (pinfunction "1_1") (pintype "passive"))
      (node (ref "U8") (pin "4") (pinfunction "FB_4") (pintype "input"))
    )
    (net (code "3") (name "/BB_L1") (class "Default")
      (node (ref "L2") (pin "1") (pinfunction "1_1") (pintype "passive"))
      (node (ref "U8") (pin "9") (pinfunction "L1_9") (pintype "passive"))
    )
    (net (code "4") (name "/BB_L2") (class "Default")
      (node (ref "L2") (pin "2") (pinfunction "2_2") (pintype "passive"))
      (node (ref "U8") (pin "7") (pinfunction "L2_7") (pintype "passive"))
    )
    (net (code "5") (name "/BOOST_SW") (class "Default")
      (node (ref "L3") (pin "2") (pinfunction "2_2") (pintype "passive"))
      (node (ref "U9") (pin "5") (pinfunction "SW_5") (pintype "passive"))
    )
    (net (code "6") (name "/BOOT0") (class "Default")
      (node (ref "R25") (pin "1") (pinfunction "1_1") (pintype "passive"))
      (node (ref "U1") (pin "94") (pinfunction "BOOT0_94") (pintype "bidirectional"))
    )
    (net (code "7") (name "/BTN1") (class "Default")
      (node (ref "C41") (pin "1") (pinfunction "1_1") (pintype "passive"))
      (node (ref "R45") (pin "2") (pinfunction "2_2") (pintype "passive"))
      (node (ref "SW1") (pin "1") (pinfunction "A_1") (pintype "passive"))
      (node (ref "SW1") (pin "3") (pinfunction "A_3") (pintype "passive"))
      (node (ref "U1") (pin "42") (pinfunction "PE11_42") (pintype "bidirectional"))
    )
    (net (code "8") (name "/BTN2") (class "Default")
      (node (ref "C42") (pin "1") (pinfunction "1_1") (pintype "passive"))
      (node (ref "R46") (pin "2") (pinfunction "2_2") (pintype "passive"))
      (node (ref "SW2") (pin "1") (pinfunction "A_1") (pintype "passive"))
      (node (ref "SW2") (pin "3") (pinfunction "A_3") (pintype "passive"))
      (node (ref "U1") (pin "43") (pinfunction "PE12_43") (pintype "bidirectional"))
    )
    (net (code "9") (name "/BUCK_BST") (class "Default")
      (node (ref "C3") (pin "1") (pinfunction "1_1") (pintype "passive"))
      (node (ref "U4") (pin "7") (pinfunction "BST_7") (pintype "passive"))
    )
    (net (code "10") (name "/BUCK_EN") (class "Default")
      (node (ref "R1") (pin "2") (pinfunction "2_2") (pintype "passive"))
      (node (ref "R2") (pin "1") (pinfunction "1_1") (pintype "passive"))
      (node (ref "U4") (pin "3") (pinfunction "EN/UVLO_3") (pintype "input"))
    )
    (net (code "11") (name "/BUCK_FB") (class "Default")
      (node (ref "C5") (pin "2") (pinfunction "2_2") (pintype "passive"))
      (node (ref "R4") (pin "2") (pinfunction "2_2") (pintype "passive"))
      (node (ref "R5") (pin "1") (pinfunction "1_1") (pintype "passive"))
      (node (ref "U4") (pin "5") (pinfunction "FB_5") (pintype "input"))
    )
    (net (code "12") (name "/BUCK_RIP") (class "Default")
      (node (ref "C4") (pin "1") (pinfunction "1_1") (pintype "passive"))
      (node (ref "C5") (pin "1") (pinfunction "1_1") (pintype "passive"))
      (node (ref "R6") (pin "2") (pinfunction "2_2") (pintype "passive"))
    )
    (net (code "13") (name "/BUCK_RON") (class "Default")
      (node (ref "R3") (pin "1") (pinfunction "1_1") (pintype "passive"))
      (node (ref "U4") (pin "4") (pinfunction "RON_4") (pintype "passive"))
    )
    (net (code "14") (name "/BUCK_SW") (class "Default")
      (node (ref "C3") (pin "2") (pinfunction "2_2") (pintype "passive"))
      (node (ref "L1") (pin "1") (pinfunction "1_1") (pintype "passive"))
      (node (ref "R6") (pin "1") (pinfunction "1_1") (pintype "passive"))
      (node (ref "U4") (pin "8") (pinfunction "SW_8") (pintype "passive"))
    )
    (net (code "15") (name "/CAN1_H_C") (class "Default")
      (node (ref "J1") (pin "7") (pinfunction "CAN_H_7") (pintype "passive"))
      (node (ref "U11") (pin "1") (pinfunction "IO1_1") (pintype "passive"))
      (node (ref "U2") (pin "7") (pinfunction "CANH_7") (pintype "bidirectional"))
    )
    (net (code "16") (name "/CAN1_L_C") (class "Default")
      (node (ref "J1") (pin "2") (pinfunction "CAN_L_2") (pintype "passive"))
      (node (ref "U11") (pin "2") (pinfunction "IO2_2") (pintype "passive"))
      (node (ref "U2") (pin "6") (pinfunction "CANL_6") (pintype "bidirectional"))
    )
    (net (code "17") (name "/CAN1_RX") (class "Default")
      (node (ref "U1") (pin "81") (pinfunction "PD0_81") (pintype "bidirectional"))
      (node (ref "U2") (pin "4") (pinfunction "RXD_4") (pintype "output"))
    )
    (net (code "18") (name "/CAN1_STBY") (class "Default")
      (node (ref "R38") (pin "2") (pinfunction "2_2") (pintype "passive"))
      (node (ref "U1") (pin "84") (pinfunction "PD3_84") (pintype "bidirectional"))
      (node (ref "U2") (pin "8") (pinfunction "STBY_8") (pintype "input"))
    )
    (net (code "19") (name "/CAN1_TX") (class "Default")
      (node (ref "U1") (pin "82") (pinfunction "PD1_82") (pintype "bidirectional"))
      (node (ref "U2") (pin "1") (pinfunction "TXD_1") (pintype "input"))
    )
    (net (code "20") (name "/CAN2_H_C") (class "Default")
      (node (ref "J2") (pin "7") (pinfunction "CAN_H_7") (pintype "passive"))
      (node (ref "U12") (pin "1") (pinfunction "IO1_1") (pintype "passive"))
      (node (ref "U3") (pin "7") (pinfunction "CANH_7") (pintype "bidirectional"))
    )
    (net (code "21") (name "/CAN2_L_C") (class "Default")
      (node (ref "J2") (pin "2") (pinfunction "CAN_L_2") (pintype "passive"))
      (node (ref "U12") (pin "2") (pinfunction "IO2_2") (pintype "passive"))
      (node (ref "U3") (pin "6") (pinfunction "CANL_6") (pintype "bidirectional"))
    )
    (net (code "22") (name "/CAN2_RX") (class "Default")
      (node (ref "U1") (pin "51") (pinfunction "PB12_51") (pintype "bidirectional"))
      (node (ref "U3") (pin "4") (pinfunction "RXD_4") (pintype "output"))
    )
    (net (code "23") (name "/CAN2_STBY") (class "Default")
      (node (ref "R39") (pin "2") (pinfunction "2_2") (pintype "passive"))
      (node (ref "U1") (pin "53") (pinfunction "PB14_53") (pintype "bidirectional"))
      (node (ref "U3") (pin "8") (pinfunction "STBY_8") (pintype "input"))
    )
    (net (code "24") (name "/CAN2_TX") (class "Default")
      (node (ref "U1") (pin "52") (pinfunction "PB13_52") (pintype "bidirectional"))
      (node (ref "U3") (pin "1") (pinfunction "TXD_1") (pintype "input"))
    )
    (net (code "25") (name "/CELL_N") (class "Default")
      (node (ref "BT1") (pin "2") (pinfunction "-_2") (pintype "passive"))
      (node (ref "C11") (pin "2") (pinfunction "2_2") (pintype "passive"))
      (node (ref "Q2") (pin "2") (pinfunction "S_2") (pintype "passive"))
      (node (ref "U6") (pin "4") (pinfunction "VSS_4") (pintype "power_in"))
    )
    (net (code "26") (name "/CELL_P") (class "Default")
      (node (ref "BT1") (pin "1") (pinfunction "+_1") (pintype "passive"))
      (node (ref "R16") (pin "1") (pinfunction "1_1") (pintype "passive"))
      (node (ref "R17") (pin "1") (pinfunction "1_1") (pintype "passive"))
      (node (ref "U7") (pin "11") (pinfunction "SENSE1+_11") (pintype "input"))
    )
    (net (code "27") (name "/CHG_DIS") (class "Default")
      (node (ref "Q4") (pin "1") (pinfunction "G_1") (pintype "input"))
      (node (ref "R14") (pin "1") (pinfunction "1_1") (pintype "passive"))
      (node (ref "U1") (pin "40") (pinfunction "PE9_40") (pintype "bidirectional"))
    )
    (net (code "28") (name "/CHG_ISET") (class "Default")
      (node (ref "R10") (pin "1") (pinfunction "1_1") (pintype "passive"))
      (node (ref "U5") (pin "2") (pinfunction "ISET_2") (pintype "passive"))
    )
    (net (code "29") (name "/CHG_PG") (class "Default")
      (node (ref "R13") (pin "2") (pinfunction "2_2") (pintype "passive"))
      (node (ref "U1") (pin "39") (pinfunction "PE8_39") (pintype "bidirectional"))
      (node (ref "U5") (pin "6") (pinfunction "/PG_6") (pintype "output"))
    )
    (net (code "30") (name "/CHG_STAT") (class "Default")
      (node (ref "R12") (pin "2") (pinfunction "2_2") (pintype "passive"))
      (node (ref "U1") (pin "38") (pinfunction "PE7_38") (pintype "bidirectional"))
      (node (ref "U5") (pin "5") (pinfunction "STAT_5") (pintype "output"))
    )
    (net (code "31") (name "/CHG_VSET") (class "Default")
      (node (ref "R11") (pin "1") (pinfunction "1_1") (pintype "passive"))
      (node (ref "U5") (pin "7") (pinfunction "VSET_7") (pintype "passive"))
    )
    (net (code "32") (name "/EXTCOMIN") (class "Default")
      (node (ref "J5") (pin "4") (pinfunction "EXTCOMIN_4") (pintype "passive"))
      (node (ref "U1") (pin "37") (pinfunction "PB2_37") (pintype "bidirectional"))
    )
    (net (code "33") (name "/FET_MID") (class "Default")
      (node (ref "Q2") (pin "3") (pinfunction "D_3") (pintype "passive"))
      (node (ref "Q3") (pin "3") (pinfunction "D_3") (pintype "passive"))
    )
    (net (code "34") (name "/I2C_SCL") (class "Default")
      (node (ref "R43") (pin "2") (pinfunction "2_2") (pintype "passive"))
      (node (ref "U1") (pin "92") (pinfunction "PB6_92") (pintype "bidirectional"))
      (node (ref "U10") (pin "3") (pinfunction "SCL_3") (pintype "input"))
      (node (ref "U7") (pin "4") (pinfunction "SCL_4") (pintype "input"))
    )
    (net (code "35") (name "/I2C_SDA") (class "Default")
      (node (ref "R44") (pin "2") (pinfunction "2_2") (pintype "passive"))
      (node (ref "U1") (pin "93") (pinfunction "PB7_93") (pintype "bidirectional"))
      (node (ref "U10") (pin "4") (pinfunction "SDA_4") (pintype "bidirectional"))
      (node (ref "U7") (pin "5") (pinfunction "SDA_5") (pintype "bidirectional"))
    )
    (net (code "36") (name "/LCD_CS") (class "Default")
      (node (ref "J5") (pin "3") (pinfunction "SCS_3") (pintype "passive"))
      (node (ref "R40") (pin "1") (pinfunction "1_1") (pintype "passive"))
      (node (ref "U1") (pin "29") (pinfunction "PA4_29") (pintype "bidirectional"))
    )
    (net (code "37") (name "/LCD_DISP") (class "Default")
      (node (ref "J5") (pin "5") (pinfunction "DISP_5") (pintype "passive"))
      (node (ref "R41") (pin "1") (pinfunction "1_1") (pintype "passive"))
      (node (ref "U1") (pin "31") (pinfunction "PA6_31") (pintype "bidirectional"))
    )
    (net (code "38") (name "/LCD_SCK") (class "Default")
      (node (ref "J5") (pin "1") (pinfunction "SCLK_1") (pintype "passive"))
      (node (ref "U1") (pin "30") (pinfunction "PA5_30") (pintype "bidirectional"))
    )
    (net (code "39") (name "/LCD_SI") (class "Default")
      (node (ref "J5") (pin "2") (pinfunction "SI_2") (pintype "passive"))
      (node (ref "U1") (pin "32") (pinfunction "PA7_32") (pintype "bidirectional"))
    )
    (net (code "40") (name "/LED_A") (class "Default")
      (node (ref "D7") (pin "1") (pinfunction "A_1") (pintype "passive"))
      (node (ref "R47") (pin "2") (pinfunction "2_2") (pintype "passive"))
    )
    (net (code "41") (name "/LED_STAT") (class "Default")
      (node (ref "R47") (pin "1") (pinfunction "1_1") (pintype "passive"))
      (node (ref "U1") (pin "44") (pinfunction "PE13_44") (pintype "bidirectional"))
    )
    (net (code "42") (name "/NRST") (class "Default")
      (node (ref "C29") (pin "1") (pinfunction "1_1") (pintype "passive"))
      (node (ref "J7") (pin "10") (pinfunction "NRST_10") (pintype "passive"))
      (node (ref "U1") (pin "14") (pinfunction "NRST_14") (pintype "bidirectional"))
    )
    (net (code "43") (name "/NTC_CHG") (class "Default")
      (node (ref "J6") (pin "1") (pinfunction "1_1") (pintype "passive"))
      (node (ref "Q4") (pin "3") (pinfunction "D_3") (pintype "passive"))
      (node (ref "U5") (pin "3") (pinfunction "TS_3") (pintype "passive"))
    )
    (net (code "44") (name "/NTC_MCU") (class "Default")
      (node (ref "C43") (pin "1") (pinfunction "1_1") (pintype "passive"))
      (node (ref "J6") (pin "2") (pinfunction "2_2") (pintype "passive"))
      (node (ref "R48") (pin "2") (pinfunction "2_2") (pintype "passive"))
      (node (ref "U1") (pin "16") (pinfunction "PC1_16") (pintype "bidirectional"))
    )
    (net (code "45") (name "/OSC_IN") (class "Default")
      (node (ref "C30") (pin "1") (pinfunction "1_1") (pintype "passive"))
      (node (ref "U1") (pin "12") (pinfunction "PH0-OSC_IN_12") (pintype "bidirectional"))
      (node (ref "Y1") (pin "1") (pinfunction "X1_1") (pintype "passive"))
    )
    (net (code "46") (name "/OSC_OUT") (class "Default")
      (node (ref "C31") (pin "1") (pinfunction "1_1") (pintype "passive"))
      (node (ref "U1") (pin "13") (pinfunction "PH1-OSC_OUT_13") (pintype "bidirectional"))
      (node (ref "Y1") (pin "3") (pinfunction "X2_3") (pintype "passive"))
    )
    (net (code "47") (name "/PAC_ADDR") (class "Default")
      (node (ref "R19") (pin "1") (pinfunction "1_1") (pintype "passive"))
      (node (ref "U7") (pin "6") (pinfunction "ADDRSEL_6") (pintype "passive"))
    )
    (net (code "48") (name "/PAC_ALERT") (class "Default")
      (node (ref "R22") (pin "2") (pinfunction "2_2") (pintype "passive"))
      (node (ref "U1") (pin "96") (pinfunction "PB9_96") (pintype "bidirectional"))
      (node (ref "U7") (pin "15") (pinfunction "GPIO/ALERT2_15") (pintype "bidirectional"))
    )
    (net (code "49") (name "/PAC_PWRDN") (class "Default")
      (node (ref "R20") (pin "2") (pinfunction "2_2") (pintype "passive"))
      (node (ref "U1") (pin "97") (pinfunction "PE0_97") (pintype "bidirectional"))
      (node (ref "U7") (pin "16") (pinfunction "PWRDN_16") (pintype "input"))
    )
    (net (code "50") (name "/PAC_SLOW") (class "Default")
      (node (ref "R21") (pin "1") (pinfunction "1_1") (pintype "passive"))
      (node (ref "U7") (pin "1") (pinfunction "SLOW/ALERT1_1") (pintype "bidirectional"))
    )
    (net (code "51") (name "/PROT_BAT") (class "Default")
      (node (ref "C11") (pin "1") (pinfunction "1_1") (pintype "passive"))
      (node (ref "R17") (pin "2") (pinfunction "2_2") (pintype "passive"))
      (node (ref "U6") (pin "5") (pinfunction "BAT_5") (pintype "power_in"))
    )
    (net (code "52") (name "/PROT_COUT") (class "Default")
      (node (ref "Q3") (pin "1") (pinfunction "G_1") (pintype "input"))
      (node (ref "U6") (pin "2") (pinfunction "COUT_2") (pintype "output"))
    )
    (net (code "53") (name "/PROT_DOUT") (class "Default")
      (node (ref "Q2") (pin "1") (pinfunction "G_1") (pintype "input"))
      (node (ref "U6") (pin "3") (pinfunction "DOUT_3") (pintype "output"))
    )
    (net (code "54") (name "/PROT_VM") (class "Default")
      (node (ref "R18") (pin "1") (pinfunction "1_1") (pintype "passive"))
      (node (ref "U6") (pin "6") (pinfunction "V-_6") (pintype "passive"))
    )
    (net (code "55") (name "/RTC_CLKOUT") (class "Default")
      (node (ref "U1") (pin "23") (pinfunction "PA0_23") (pintype "bidirectional"))
      (node (ref "U10") (pin "1") (pinfunction "CLKOUT_1") (pintype "output"))
    )
    (net (code "56") (name "/RTC_INT") (class "Default")
      (node (ref "R42") (pin "2") (pinfunction "2_2") (pintype "passive"))
      (node (ref "U1") (pin "95") (pinfunction "PB8_95") (pintype "bidirectional"))
      (node (ref "U10") (pin "2") (pinfunction "INT_2") (pintype "output"))
    )
    (net (code "57") (name "/SD_CD") (class "Default")
      (node (ref "J4") (pin "9") (pinfunction "CD_A_9") (pintype "passive"))
      (node (ref "R37") (pin "2") (pinfunction "2_2") (pintype "passive"))
      (node (ref "U1") (pin "85") (pinfunction "PD4_85") (pintype "bidirectional"))
    )
    (net (code "58") (name "/SD_CLK") (class "Default")
      (node (ref "J4") (pin "5") (pinfunction "CLK_5") (pintype "passive"))
      (node (ref "R36") (pin "2") (pinfunction "2_2") (pintype "passive"))
    )
    (net (code "59") (name "/SD_CLK_MCU") (class "Default")
      (node (ref "R36") (pin "1") (pinfunction "1_1") (pintype "passive"))
      (node (ref "U1") (pin "80") (pinfunction "PC12_80") (pintype "bidirectional"))
    )
    (net (code "60") (name "/SD_CMD") (class "Default")
      (node (ref "J4") (pin "3") (pinfunction "CMD_3") (pintype "passive"))
      (node (ref "R31") (pin "2") (pinfunction "2_2") (pintype "passive"))
      (node (ref "U1") (pin "83") (pinfunction "PD2_83") (pintype "bidirectional"))
    )
    (net (code "61") (name "/SD_D0") (class "Default")
      (node (ref "J4") (pin "7") (pinfunction "DAT0_7") (pintype "passive"))
      (node (ref "R32") (pin "2") (pinfunction "2_2") (pintype "passive"))
      (node (ref "U1") (pin "65") (pinfunction "PC8_65") (pintype "bidirectional"))
    )
    (net (code "62") (name "/SD_D1") (class "Default")
      (node (ref "J4") (pin "8") (pinfunction "DAT1_8") (pintype "passive"))
      (node (ref "R33") (pin "2") (pinfunction "2_2") (pintype "passive"))
      (node (ref "U1") (pin "66") (pinfunction "PC9_66") (pintype "bidirectional"))
    )
    (net (code "63") (name "/SD_D2") (class "Default")
      (node (ref "J4") (pin "1") (pinfunction "DAT2_1") (pintype "passive"))
      (node (ref "R34") (pin "2") (pinfunction "2_2") (pintype "passive"))
      (node (ref "U1") (pin "78") (pinfunction "PC10_78") (pintype "bidirectional"))
    )
    (net (code "64") (name "/SD_D3") (class "Default")
      (node (ref "J4") (pin "2") (pinfunction "CD/DAT3_2") (pintype "passive"))
      (node (ref "R35") (pin "2") (pinfunction "2_2") (pintype "passive"))
      (node (ref "U1") (pin "79") (pinfunction "PC11_79") (pintype "bidirectional"))
    )
    (net (code "65") (name "/SD_PWR_EN_N") (class "Default")
      (node (ref "Q5") (pin "1") (pinfunction "G_1") (pintype "input"))
      (node (ref "R30") (pin "2") (pinfunction "2_2") (pintype "passive"))
      (node (ref "U1") (pin "86") (pinfunction "PD5_86") (pintype "bidirectional"))
    )
    (net (code "66") (name "/SD_VDD") (class "Default")
      (node (ref "C32") (pin "1") (pinfunction "1_1") (pintype "passive"))
      (node (ref "C33") (pin "1") (pinfunction "1_1") (pintype "passive"))
      (node (ref "J4") (pin "4") (pinfunction "VDD_4") (pintype "passive"))
      (node (ref "Q5") (pin "3") (pinfunction "D_3") (pintype "passive"))
      (node (ref "R31") (pin "1") (pinfunction "1_1") (pintype "passive"))
      (node (ref "R32") (pin "1") (pinfunction "1_1") (pintype "passive"))
      (node (ref "R33") (pin "1") (pinfunction "1_1") (pintype "passive"))
      (node (ref "R34") (pin "1") (pinfunction "1_1") (pintype "passive"))
      (node (ref "R35") (pin "1") (pinfunction "1_1") (pintype "passive"))
    )
    (net (code "67") (name "/SWCLK") (class "Default")
      (node (ref "J7") (pin "4") (pinfunction "SWCLK_4") (pintype "passive"))
      (node (ref "U1") (pin "76") (pinfunction "PA14_76") (pintype "bidirectional"))
    )
    (net (code "68") (name "/SWDIO") (class "Default")
      (node (ref "J7") (pin "2") (pinfunction "SWDIO_2") (pintype "passive"))
      (node (ref "U1") (pin "72") (pinfunction "PA13_72") (pintype "bidirectional"))
    )
    (net (code "69") (name "/SWO") (class "Default")
      (node (ref "J7") (pin "6") (pinfunction "SWO_6") (pintype "passive"))
      (node (ref "U1") (pin "89") (pinfunction "PB3_89") (pintype "bidirectional"))
    )
    (net (code "70") (name "/USB_CC1") (class "Default")
      (node (ref "J3") (pin "A5") (pinfunction "CC1_A5") (pintype "passive"))
      (node (ref "R26") (pin "1") (pinfunction "1_1") (pintype "passive"))
    )
    (net (code "71") (name "/USB_CC2") (class "Default")
      (node (ref "J3") (pin "B5") (pinfunction "CC2_B5") (pintype "passive"))
      (node (ref "R27") (pin "1") (pinfunction "1_1") (pintype "passive"))
    )
    (net (code "72") (name "/USB_DM") (class "Default")
      (node (ref "J3") (pin "A7") (pinfunction "DN1_A7") (pintype "passive"))
      (node (ref "J3") (pin "B7") (pinfunction "DN2_B7") (pintype "passive"))
      (node (ref "U1") (pin "70") (pinfunction "PA11_70") (pintype "bidirectional"))
      (node (ref "U13") (pin "2") (pinfunction "IO2_2") (pintype "passive"))
    )
    (net (code "73") (name "/USB_DP") (class "Default")
      (node (ref "J3") (pin "A6") (pinfunction "DP1_A6") (pintype "passive"))
      (node (ref "J3") (pin "B6") (pinfunction "DP2_B6") (pintype "passive"))
      (node (ref "U1") (pin "71") (pinfunction "PA12_71") (pintype "bidirectional"))
      (node (ref "U13") (pin "1") (pinfunction "IO1_1") (pintype "passive"))
    )
    (net (code "74") (name "/V1_IN") (class "Default")
      (node (ref "D1") (pin "2") (pinfunction "A_2") (pintype "passive"))
      (node (ref "J1") (pin "9") (pinfunction "V+_9") (pintype "passive"))
    )
    (net (code "75") (name "/V2_IN") (class "Default")
      (node (ref "D2") (pin "2") (pinfunction "A_2") (pintype "passive"))
      (node (ref "J2") (pin "9") (pinfunction "V+_9") (pintype "passive"))
    )
    (net (code "76") (name "/VBACKUP") (class "Default")
      (node (ref "BT2") (pin "1") (pinfunction "+_1") (pintype "passive"))
      (node (ref "U10") (pin "6") (pinfunction "VBACKUP_6") (pintype "power_in"))
    )
    (net (code "77") (name "/VBAT") (class "Default")
      (node (ref "C9") (pin "1") (pinfunction "1_1") (pintype "passive"))
      (node (ref "Q1") (pin "3") (pinfunction "D_3") (pintype "passive"))
      (node (ref "R16") (pin "2") (pinfunction "2_2") (pintype "passive"))
      (node (ref "U5") (pin "8") (pinfunction "OUT_8") (pintype "power_in"))
      (node (ref "U7") (pin "12") (pinfunction "SENSE1-_12") (pintype "input"))
    )
    (net (code "78") (name "/VBUS") (class "Default")
      (node (ref "D5") (pin "2") (pinfunction "A_2") (pintype "passive"))
      (node (ref "J3") (pin "A4") (pinfunction "VBUS_A4") (pintype "passive"))
      (node (ref "J3") (pin "A9") (pinfunction "VBUS_A9") (pintype "passive"))
      (node (ref "R28") (pin "1") (pinfunction "1_1") (pintype "passive"))
    )
    (net (code "79") (name "/VBUS_DET") (class "Default")
      (node (ref "R28") (pin "2") (pinfunction "2_2") (pintype "passive"))
      (node (ref "R29") (pin "1") (pinfunction "1_1") (pintype "passive"))
      (node (ref "U1") (pin "68") (pinfunction "PA9_68") (pintype "bidirectional"))
    )
    (net (code "80") (name "/VCAP1") (class "Default")
      (node (ref "C19") (pin "1") (pinfunction "1_1") (pintype "passive"))
      (node (ref "U1") (pin "48") (pinfunction "VCAP_48") (pintype "power_in"))
    )
    (net (code "81") (name "/VCAP2") (class "Default")
      (node (ref "C20") (pin "1") (pinfunction "1_1") (pintype "passive"))
      (node (ref "U1") (pin "98") (pinfunction "VCAP_98") (pintype "power_in"))
    )
    (net (code "82") (name "/VCHG") (class "Default")
      (node (ref "C8") (pin "1") (pinfunction "1_1") (pintype "passive"))
      (node (ref "D4") (pin "1") (pinfunction "K_1") (pintype "passive"))
      (node (ref "D5") (pin "1") (pinfunction "K_1") (pintype "passive"))
      (node (ref "D6") (pin "2") (pinfunction "A_2") (pintype "passive"))
      (node (ref "Q1") (pin "1") (pinfunction "G_1") (pintype "input"))
      (node (ref "R15") (pin "1") (pinfunction "1_1") (pintype "passive"))
      (node (ref "U5") (pin "1") (pinfunction "IN_1") (pintype "power_in"))
    )
    (net (code "83") (name "/VEH_PG") (class "Default")
      (node (ref "R7") (pin "2") (pinfunction "2_2") (pintype "passive"))
      (node (ref "U1") (pin "41") (pinfunction "PE10_41") (pintype "bidirectional"))
      (node (ref "U4") (pin "6") (pinfunction "PGOOD_6") (pintype "output"))
    )
    (net (code "84") (name "/VIN_P") (class "Default")
      (node (ref "C1") (pin "1") (pinfunction "1_1") (pintype "passive"))
      (node (ref "C2") (pin "1") (pinfunction "1_1") (pintype "passive"))
      (node (ref "D1") (pin "1") (pinfunction "K_1") (pintype "passive"))
      (node (ref "D2") (pin "1") (pinfunction "K_1") (pintype "passive"))
      (node (ref "D3") (pin "1") (pinfunction "K_1") (pintype "passive"))
      (node (ref "R1") (pin "1") (pinfunction "1_1") (pintype "passive"))
      (node (ref "R8") (pin "1") (pinfunction "1_1") (pintype "passive"))
      (node (ref "U4") (pin "2") (pinfunction "VIN_2") (pintype "power_in"))
    )
    (net (code "85") (name "/VIN_SENSE") (class "Default")
      (node (ref "C7") (pin "1") (pinfunction "1_1") (pintype "passive"))
      (node (ref "R8") (pin "2") (pinfunction "2_2") (pintype "passive"))
      (node (ref "R9") (pin "1") (pinfunction "1_1") (pintype "passive"))
      (node (ref "U1") (pin "15") (pinfunction "PC0_15") (pintype "bidirectional"))
    )
    (net (code "86") (name "/VSYS") (class "Default")
      (node (ref "C10") (pin "1") (pinfunction "1_1") (pintype "passive"))
      (node (ref "C13") (pin "1") (pinfunction "1_1") (pintype "passive"))
      (node (ref "C16") (pin "1") (pinfunction "1_1") (pintype "passive"))
      (node (ref "D6") (pin "1") (pinfunction "K_1") (pintype "passive"))
      (node (ref "L3") (pin "1") (pinfunction "1_1") (pintype "passive"))
      (node (ref "Q1") (pin "2") (pinfunction "S_2") (pintype "passive"))
      (node (ref "U8") (pin "1") (pinfunction "EN_1") (pintype "input"))
      (node (ref "U8") (pin "10") (pinfunction "VIN_10") (pintype "power_in"))
      (node (ref "U9") (pin "4") (pinfunction "EN_4") (pintype "input"))
      (node (ref "U9") (pin "6") (pinfunction "VIN_6") (pintype "power_in"))
    )
    (net (code "87") (name "3V3") (class "Default")
      (node (ref "C12") (pin "1") (pinfunction "1_1") (pintype "passive"))
      (node (ref "C14") (pin "1") (pinfunction "1_1") (pintype "passive"))
      (node (ref "C15") (pin "1") (pinfunction "1_1") (pintype "passive"))
      (node (ref "C21") (pin "1") (pinfunction "1_1") (pintype "passive"))
      (node (ref "C22") (pin "1") (pinfunction "1_1") (pintype "passive"))
      (node (ref "C23") (pin "1") (pinfunction "1_1") (pintype "passive"))
      (node (ref "C24") (pin "1") (pinfunction "1_1") (pintype "passive"))
      (node (ref "C25") (pin "1") (pinfunction "1_1") (pintype "passive"))
      (node (ref "C26") (pin "1") (pinfunction "1_1") (pintype "passive"))
      (node (ref "C27") (pin "1") (pinfunction "1_1") (pintype "passive"))
      (node (ref "C28") (pin "1") (pinfunction "1_1") (pintype "passive"))
      (node (ref "C35") (pin "1") (pinfunction "1_1") (pintype "passive"))
      (node (ref "C37") (pin "1") (pinfunction "1_1") (pintype "passive"))
      (node (ref "C40") (pin "1") (pinfunction "1_1") (pintype "passive"))
      (node (ref "J7") (pin "1") (pinfunction "VTREF_1") (pintype "passive"))
      (node (ref "Q5") (pin "2") (pinfunction "S_2") (pintype "passive"))
      (node (ref "R12") (pin "1") (pinfunction "1_1") (pintype "passive"))
      (node (ref "R13") (pin "1") (pinfunction "1_1") (pintype "passive"))
      (node (ref "R20") (pin "1") (pinfunction "1_1") (pintype "passive"))
      (node (ref "R22") (pin "1") (pinfunction "1_1") (pintype "passive"))
      (node (ref "R23") (pin "1") (pinfunction "1_1") (pintype "passive"))
      (node (ref "R30") (pin "1") (pinfunction "1_1") (pintype "passive"))
      (node (ref "R37") (pin "1") (pinfunction "1_1") (pintype "passive"))
      (node (ref "R38") (pin "1") (pinfunction "1_1") (pintype "passive"))
      (node (ref "R39") (pin "1") (pinfunction "1_1") (pintype "passive"))
      (node (ref "R42") (pin "1") (pinfunction "1_1") (pintype "passive"))
      (node (ref "R43") (pin "1") (pinfunction "1_1") (pintype "passive"))
      (node (ref "R44") (pin "1") (pinfunction "1_1") (pintype "passive"))
      (node (ref "R45") (pin "1") (pinfunction "1_1") (pintype "passive"))
      (node (ref "R46") (pin "1") (pinfunction "1_1") (pintype "passive"))
      (node (ref "R48") (pin "1") (pinfunction "1_1") (pintype "passive"))
      (node (ref "R7") (pin "1") (pinfunction "1_1") (pintype "passive"))
      (node (ref "U1") (pin "100") (pinfunction "VDD_100") (pintype "power_in"))
      (node (ref "U1") (pin "11") (pinfunction "VDD_11") (pintype "power_in"))
      (node (ref "U1") (pin "21") (pinfunction "VREF+_21") (pintype "power_in"))
      (node (ref "U1") (pin "22") (pinfunction "VDDA_22") (pintype "power_in"))
      (node (ref "U1") (pin "28") (pinfunction "VDD_28") (pintype "power_in"))
      (node (ref "U1") (pin "50") (pinfunction "VDD_50") (pintype "power_in"))
      (node (ref "U1") (pin "6") (pinfunction "VBAT_6") (pintype "power_in"))
      (node (ref "U1") (pin "73") (pinfunction "VDDUSB_73") (pintype "power_in"))
      (node (ref "U1") (pin "75") (pinfunction "VDD_75") (pintype "power_in"))
      (node (ref "U10") (pin "7") (pinfunction "VDD_7") (pintype "power_in"))
      (node (ref "U2") (pin "5") (pinfunction "VIO_5") (pintype "power_in"))
      (node (ref "U3") (pin "5") (pinfunction "VIO_5") (pintype "power_in"))
      (node (ref "U7") (pin "2") (pinfunction "VDD_2") (pintype "power_in"))
      (node (ref "U8") (pin "6") (pinfunction "VOUT_6") (pintype "power_in"))
    )
    (net (code "88") (name "5V_AUX") (class "Default")
      (node (ref "C17") (pin "1") (pinfunction "1_1") (pintype "passive"))
      (node (ref "C18") (pin "1") (pinfunction "1_1") (pintype "passive"))
      (node (ref "C34") (pin "1") (pinfunction "1_1") (pintype "passive"))
      (node (ref "C36") (pin "1") (pinfunction "1_1") (pintype "passive"))
      (node (ref "C38") (pin "1") (pinfunction "1_1") (pintype "passive"))
      (node (ref "C39") (pin "1") (pinfunction "1_1") (pintype "passive"))
      (node (ref "J5") (pin "6") (pinfunction "VDDA_6") (pintype "passive"))
      (node (ref "J5") (pin "7") (pinfunction "VDD_7") (pintype "passive"))
      (node (ref "J5") (pin "8") (pinfunction "EXTMODE_8") (pintype "passive"))
      (node (ref "U2") (pin "3") (pinfunction "VDD_3") (pintype "power_in"))
      (node (ref "U3") (pin "3") (pinfunction "VDD_3") (pintype "power_in"))
      (node (ref "U9") (pin "2") (pinfunction "VOUT_2") (pintype "power_in"))
    )
    (net (code "89") (name "GND") (class "Default")
      (node (ref "BT2") (pin "2") (pinfunction "-_2") (pintype "passive"))
      (node (ref "C1") (pin "2") (pinfunction "2_2") (pintype "passive"))
      (node (ref "C10") (pin "2") (pinfunction "2_2") (pintype "passive"))
      (node (ref "C12") (pin "2") (pinfunction "2_2") (pintype "passive"))
      (node (ref "C13") (pin "2") (pinfunction "2_2") (pintype "passive"))
      (node (ref "C14") (pin "2") (pinfunction "2_2") (pintype "passive"))
      (node (ref "C15") (pin "2") (pinfunction "2_2") (pintype "passive"))
      (node (ref "C16") (pin "2") (pinfunction "2_2") (pintype "passive"))
      (node (ref "C17") (pin "2") (pinfunction "2_2") (pintype "passive"))
      (node (ref "C18") (pin "2") (pinfunction "2_2") (pintype "passive"))
      (node (ref "C19") (pin "2") (pinfunction "2_2") (pintype "passive"))
      (node (ref "C2") (pin "2") (pinfunction "2_2") (pintype "passive"))
      (node (ref "C20") (pin "2") (pinfunction "2_2") (pintype "passive"))
      (node (ref "C21") (pin "2") (pinfunction "2_2") (pintype "passive"))
      (node (ref "C22") (pin "2") (pinfunction "2_2") (pintype "passive"))
      (node (ref "C23") (pin "2") (pinfunction "2_2") (pintype "passive"))
      (node (ref "C24") (pin "2") (pinfunction "2_2") (pintype "passive"))
      (node (ref "C25") (pin "2") (pinfunction "2_2") (pintype "passive"))
      (node (ref "C26") (pin "2") (pinfunction "2_2") (pintype "passive"))
      (node (ref "C27") (pin "2") (pinfunction "2_2") (pintype "passive"))
      (node (ref "C28") (pin "2") (pinfunction "2_2") (pintype "passive"))
      (node (ref "C29") (pin "2") (pinfunction "2_2") (pintype "passive"))
      (node (ref "C30") (pin "2") (pinfunction "2_2") (pintype "passive"))
      (node (ref "C31") (pin "2") (pinfunction "2_2") (pintype "passive"))
      (node (ref "C32") (pin "2") (pinfunction "2_2") (pintype "passive"))
      (node (ref "C33") (pin "2") (pinfunction "2_2") (pintype "passive"))
      (node (ref "C34") (pin "2") (pinfunction "2_2") (pintype "passive"))
      (node (ref "C35") (pin "2") (pinfunction "2_2") (pintype "passive"))
      (node (ref "C36") (pin "2") (pinfunction "2_2") (pintype "passive"))
      (node (ref "C37") (pin "2") (pinfunction "2_2") (pintype "passive"))
      (node (ref "C38") (pin "2") (pinfunction "2_2") (pintype "passive"))
      (node (ref "C39") (pin "2") (pinfunction "2_2") (pintype "passive"))
      (node (ref "C40") (pin "2") (pinfunction "2_2") (pintype "passive"))
      (node (ref "C41") (pin "2") (pinfunction "2_2") (pintype "passive"))
      (node (ref "C42") (pin "2") (pinfunction "2_2") (pintype "passive"))
      (node (ref "C43") (pin "2") (pinfunction "2_2") (pintype "passive"))
      (node (ref "C6") (pin "2") (pinfunction "2_2") (pintype "passive"))
      (node (ref "C7") (pin "2") (pinfunction "2_2") (pintype "passive"))
      (node (ref "C8") (pin "2") (pinfunction "2_2") (pintype "passive"))
      (node (ref "C9") (pin "2") (pinfunction "2_2") (pintype "passive"))
      (node (ref "D3") (pin "2") (pinfunction "A_2") (pintype "passive"))
      (node (ref "D7") (pin "2") (pinfunction "K_2") (pintype "passive"))
      (node (ref "J1") (pin "3") (pinfunction "CAN_GND_3") (pintype "passive"))
      (node (ref "J1") (pin "5") (pinfunction "SHLD_5") (pintype "passive"))
      (node (ref "J1") (pin "6") (pinfunction "GND_6") (pintype "passive"))
      (node (ref "J1") (pin "MH") (pinfunction "MH_MH") (pintype "passive"))
      (node (ref "J2") (pin "3") (pinfunction "CAN_GND_3") (pintype "passive"))
      (node (ref "J2") (pin "5") (pinfunction "SHLD_5") (pintype "passive"))
      (node (ref "J2") (pin "6") (pinfunction "GND_6") (pintype "passive"))
      (node (ref "J2") (pin "MH") (pinfunction "MH_MH") (pintype "passive"))
      (node (ref "J3") (pin "A1") (pinfunction "GND_A1") (pintype "passive"))
      (node (ref "J3") (pin "A12") (pinfunction "GND_A12") (pintype "passive"))
      (node (ref "J3") (pin "SH") (pinfunction "SHIELD_SH") (pintype "passive"))
      (node (ref "J4") (pin "10") (pinfunction "CD_B_10") (pintype "passive"))
      (node (ref "J4") (pin "6") (pinfunction "VSS_6") (pintype "passive"))
      (node (ref "J4") (pin "SH") (pinfunction "SHIELD_SH") (pintype "passive"))
      (node (ref "J5") (pin "10") (pinfunction "VSSA_10") (pintype "passive"))
      (node (ref "J5") (pin "9") (pinfunction "VSS_9") (pintype "passive"))
      (node (ref "J5") (pin "MP") (pinfunction "MP_MP") (pintype "passive"))
      (node (ref "J6") (pin "3") (pinfunction "3_3") (pintype "passive"))
      (node (ref "J6") (pin "MP") (pinfunction "MP_MP") (pintype "passive"))
      (node (ref "J7") (pin "3") (pinfunction "GND_3") (pintype "passive"))
      (node (ref "J7") (pin "5") (pinfunction "GND_5") (pintype "passive"))
      (node (ref "J7") (pin "9") (pinfunction "GND_DET_9") (pintype "passive"))
      (node (ref "Q3") (pin "2") (pinfunction "S_2") (pintype "passive"))
      (node (ref "Q4") (pin "2") (pinfunction "S_2") (pintype "passive"))
      (node (ref "R10") (pin "2") (pinfunction "2_2") (pintype "passive"))
      (node (ref "R11") (pin "2") (pinfunction "2_2") (pintype "passive"))
      (node (ref "R14") (pin "2") (pinfunction "2_2") (pintype "passive"))
      (node (ref "R15") (pin "2") (pinfunction "2_2") (pintype "passive"))
      (node (ref "R18") (pin "2") (pinfunction "2_2") (pintype "passive"))
      (node (ref "R19") (pin "2") (pinfunction "2_2") (pintype "passive"))
      (node (ref "R2") (pin "2") (pinfunction "2_2") (pintype "passive"))
      (node (ref "R21") (pin "2") (pinfunction "2_2") (pintype "passive"))
      (node (ref "R24") (pin "2") (pinfunction "2_2") (pintype "passive"))
      (node (ref "R25") (pin "2") (pinfunction "2_2") (pintype "passive"))
      (node (ref "R26") (pin "2") (pinfunction "2_2") (pintype "passive"))
      (node (ref "R27") (pin "2") (pinfunction "2_2") (pintype "passive"))
      (node (ref "R29") (pin "2") (pinfunction "2_2") (pintype "passive"))
      (node (ref "R3") (pin "2") (pinfunction "2_2") (pintype "passive"))
      (node (ref "R40") (pin "2") (pinfunction "2_2") (pintype "passive"))
      (node (ref "R41") (pin "2") (pinfunction "2_2") (pintype "passive"))
      (node (ref "R5") (pin "2") (pinfunction "2_2") (pintype "passive"))
      (node (ref "R9") (pin "2") (pinfunction "2_2") (pintype "passive"))
      (node (ref "SW1") (pin "2") (pinfunction "B_2") (pintype "passive"))
      (node (ref "SW1") (pin "4") (pinfunction "B_4") (pintype "passive"))
      (node (ref "SW2") (pin "2") (pinfunction "B_2") (pintype "passive"))
      (node (ref "SW2") (pin "4") (pinfunction "B_4") (pintype "passive"))
      (node (ref "U1") (pin "10") (pinfunction "VSS_10") (pintype "power_in"))
      (node (ref "U1") (pin "19") (pinfunction "VSSA_19") (pintype "power_in"))
      (node (ref "U1") (pin "20") (pinfunction "VREF-_20") (pintype "power_in"))
      (node (ref "U1") (pin "27") (pinfunction "VSS_27") (pintype "power_in"))
      (node (ref "U1") (pin "49") (pinfunction "VSS_49") (pintype "power_in"))
      (node (ref "U1") (pin "74") (pinfunction "VSS_74") (pintype "power_in"))
      (node (ref "U1") (pin "99") (pinfunction "VSS_99") (pintype "power_in"))
      (node (ref "U10") (pin "5") (pinfunction "VSS_5") (pintype "power_in"))
      (node (ref "U10") (pin "8") (pinfunction "EVI_8") (pintype "input"))
      (node (ref "U11") (pin "3") (pinfunction "GND_3") (pintype "passive"))
      (node (ref "U12") (pin "3") (pinfunction "GND_3") (pintype "passive"))
      (node (ref "U13") (pin "3") (pinfunction "GND_3") (pintype "passive"))
      (node (ref "U2") (pin "2") (pinfunction "VSS_2") (pintype "power_in"))
      (node (ref "U3") (pin "2") (pinfunction "VSS_2") (pintype "power_in"))
      (node (ref "U4") (pin "1") (pinfunction "GND_1") (pintype "power_in"))
      (node (ref "U4") (pin "9") (pinfunction "EP_9") (pintype "power_in"))
      (node (ref "U5") (pin "4") (pinfunction "GND_4") (pintype "power_in"))
      (node (ref "U5") (pin "9") (pinfunction "EP_9") (pintype "power_in"))
      (node (ref "U7") (pin "10") (pinfunction "SENSE4+_10") (pintype "input"))
      (node (ref "U7") (pin "13") (pinfunction "SENSE2+_13") (pintype "input"))
      (node (ref "U7") (pin "14") (pinfunction "SENSE2-_14") (pintype "input"))
      (node (ref "U7") (pin "17") (pinfunction "EP_17") (pintype "passive"))
      (node (ref "U7") (pin "3") (pinfunction "GND_3") (pintype "power_in"))
      (node (ref "U7") (pin "7") (pinfunction "SENSE3-_7") (pintype "input"))
      (node (ref "U7") (pin "8") (pinfunction "SENSE3+_8") (pintype "input"))
      (node (ref "U7") (pin "9") (pinfunction "SENSE4-_9") (pintype "input"))
      (node (ref "U8") (pin "2") (pinfunction "MODE_2") (pintype "input"))
      (node (ref "U8") (pin "3") (pinfunction "AGND_3") (pintype "power_in"))
      (node (ref "U8") (pin "8") (pinfunction "GND_8") (pintype "power_in"))
      (node (ref "U9") (pin "1") (pinfunction "GND_1") (pintype "power_in"))
      (node (ref "U9") (pin "3") (pinfunction "FB_3") (pintype "input"))
      (node (ref "U9") (pin "7") (pinfunction "EP_7") (pintype "power_in"))
      (node (ref "Y1") (pin "2") (pinfunction "GND_2") (pintype "passive"))
      (node (ref "Y1") (pin "4") (pinfunction "GND_4") (pintype "passive"))
    )
    (net (code "90") (name "unconnected-(J1-Pad1)") (class "Default")
      (node (ref "J1") (pin "1") (pinfunction "1_1") (pintype "passive+no_connect"))
    )
    (net (code "91") (name "unconnected-(J1-Pad4)") (class "Default")
      (node (ref "J1") (pin "4") (pinfunction "4_4") (pintype "passive+no_connect"))
    )
    (net (code "92") (name "unconnected-(J1-Pad8)") (class "Default")
      (node (ref "J1") (pin "8") (pinfunction "8_8") (pintype "passive+no_connect"))
    )
    (net (code "93") (name "unconnected-(J2-Pad1)") (class "Default")
      (node (ref "J2") (pin "1") (pinfunction "1_1") (pintype "passive+no_connect"))
    )
    (net (code "94") (name "unconnected-(J2-Pad4)") (class "Default")
      (node (ref "J2") (pin "4") (pinfunction "4_4") (pintype "passive+no_connect"))
    )
    (net (code "95") (name "unconnected-(J2-Pad8)") (class "Default")
      (node (ref "J2") (pin "8") (pinfunction "8_8") (pintype "passive+no_connect"))
    )
    (net (code "96") (name "unconnected-(J3-SBU1-PadA8)") (class "Default")
      (node (ref "J3") (pin "A8") (pinfunction "SBU1_A8") (pintype "passive+no_connect"))
    )
    (net (code "97") (name "unconnected-(J3-SBU2-PadB8)") (class "Default")
      (node (ref "J3") (pin "B8") (pinfunction "SBU2_B8") (pintype "passive+no_connect"))
    )
    (net (code "98") (name "unconnected-(J7-KEY-Pad7)") (class "Default")
      (node (ref "J7") (pin "7") (pinfunction "KEY_7") (pintype "passive+no_connect"))
    )
    (net (code "99") (name "unconnected-(J7-NC-Pad8)") (class "Default")
      (node (ref "J7") (pin "8") (pinfunction "NC_8") (pintype "passive+no_connect"))
    )
    (net (code "100") (name "unconnected-(U1-PA1-Pad24)") (class "Default")
      (node (ref "U1") (pin "24") (pinfunction "PA1_24") (pintype "bidirectional+no_connect"))
    )
    (net (code "101") (name "unconnected-(U1-PA2-Pad25)") (class "Default")
      (node (ref "U1") (pin "25") (pinfunction "PA2_25") (pintype "bidirectional+no_connect"))
    )
    (net (code "102") (name "unconnected-(U1-PA3-Pad26)") (class "Default")
      (node (ref "U1") (pin "26") (pinfunction "PA3_26") (pintype "bidirectional+no_connect"))
    )
    (net (code "103") (name "unconnected-(U1-PA8-Pad67)") (class "Default")
      (node (ref "U1") (pin "67") (pinfunction "PA8_67") (pintype "bidirectional+no_connect"))
    )
    (net (code "104") (name "unconnected-(U1-PA10-Pad69)") (class "Default")
      (node (ref "U1") (pin "69") (pinfunction "PA10_69") (pintype "bidirectional+no_connect"))
    )
    (net (code "105") (name "unconnected-(U1-PA15-Pad77)") (class "Default")
      (node (ref "U1") (pin "77") (pinfunction "PA15_77") (pintype "bidirectional+no_connect"))
    )
    (net (code "106") (name "unconnected-(U1-PB0-Pad35)") (class "Default")
      (node (ref "U1") (pin "35") (pinfunction "PB0_35") (pintype "bidirectional+no_connect"))
    )
    (net (code "107") (name "unconnected-(U1-PB1-Pad36)") (class "Default")
      (node (ref "U1") (pin "36") (pinfunction "PB1_36") (pintype "bidirectional+no_connect"))
    )
    (net (code "108") (name "unconnected-(U1-PB4-Pad90)") (class "Default")
      (node (ref "U1") (pin "90") (pinfunction "PB4_90") (pintype "bidirectional+no_connect"))
    )
    (net (code "109") (name "unconnected-(U1-PB5-Pad91)") (class "Default")
      (node (ref "U1") (pin "91") (pinfunction "PB5_91") (pintype "bidirectional+no_connect"))
    )
    (net (code "110") (name "unconnected-(U1-PB10-Pad47)") (class "Default")
      (node (ref "U1") (pin "47") (pinfunction "PB10_47") (pintype "bidirectional+no_connect"))
    )
    (net (code "111") (name "unconnected-(U1-PB15-Pad54)") (class "Default")
      (node (ref "U1") (pin "54") (pinfunction "PB15_54") (pintype "bidirectional+no_connect"))
    )
    (net (code "112") (name "unconnected-(U1-PC2-Pad17)") (class "Default")
      (node (ref "U1") (pin "17") (pinfunction "PC2_17") (pintype "bidirectional+no_connect"))
    )
    (net (code "113") (name "unconnected-(U1-PC3-Pad18)") (class "Default")
      (node (ref "U1") (pin "18") (pinfunction "PC3_18") (pintype "bidirectional+no_connect"))
    )
    (net (code "114") (name "unconnected-(U1-PC4-Pad33)") (class "Default")
      (node (ref "U1") (pin "33") (pinfunction "PC4_33") (pintype "bidirectional+no_connect"))
    )
    (net (code "115") (name "unconnected-(U1-PC5-Pad34)") (class "Default")
      (node (ref "U1") (pin "34") (pinfunction "PC5_34") (pintype "bidirectional+no_connect"))
    )
    (net (code "116") (name "unconnected-(U1-PC6-Pad63)") (class "Default")
      (node (ref "U1") (pin "63") (pinfunction "PC6_63") (pintype "bidirectional+no_connect"))
    )
    (net (code "117") (name "unconnected-(U1-PC7-Pad64)") (class "Default")
      (node (ref "U1") (pin "64") (pinfunction "PC7_64") (pintype "bidirectional+no_connect"))
    )
    (net (code "118") (name "unconnected-(U1-PC13-Pad7)") (class "Default")
      (node (ref "U1") (pin "7") (pinfunction "PC13_7") (pintype "bidirectional+no_connect"))
    )
    (net (code "119") (name "unconnected-(U1-PC14-OSC32_IN-Pad8)") (class "Default")
      (node (ref "U1") (pin "8") (pinfunction "PC14-OSC32_IN_8") (pintype "bidirectional+no_connect"))
    )
    (net (code "120") (name "unconnected-(U1-PC15-OSC32_OUT-Pad9)") (class "Default")
      (node (ref "U1") (pin "9") (pinfunction "PC15-OSC32_OUT_9") (pintype "bidirectional+no_connect"))
    )
    (net (code "121") (name "unconnected-(U1-PD6-Pad87)") (class "Default")
      (node (ref "U1") (pin "87") (pinfunction "PD6_87") (pintype "bidirectional+no_connect"))
    )
    (net (code "122") (name "unconnected-(U1-PD7-Pad88)") (class "Default")
      (node (ref "U1") (pin "88") (pinfunction "PD7_88") (pintype "bidirectional+no_connect"))
    )
    (net (code "123") (name "unconnected-(U1-PD8-Pad55)") (class "Default")
      (node (ref "U1") (pin "55") (pinfunction "PD8_55") (pintype "bidirectional+no_connect"))
    )
    (net (code "124") (name "unconnected-(U1-PD9-Pad56)") (class "Default")
      (node (ref "U1") (pin "56") (pinfunction "PD9_56") (pintype "bidirectional+no_connect"))
    )
    (net (code "125") (name "unconnected-(U1-PD10-Pad57)") (class "Default")
      (node (ref "U1") (pin "57") (pinfunction "PD10_57") (pintype "bidirectional+no_connect"))
    )
    (net (code "126") (name "unconnected-(U1-PD11-Pad58)") (class "Default")
      (node (ref "U1") (pin "58") (pinfunction "PD11_58") (pintype "bidirectional+no_connect"))
    )
    (net (code "127") (name "unconnected-(U1-PD12-Pad59)") (class "Default")
      (node (ref "U1") (pin "59") (pinfunction "PD12_59") (pintype "bidirectional+no_connect"))
    )
    (net (code "128") (name "unconnected-(U1-PD13-Pad60)") (class "Default")
      (node (ref "U1") (pin "60") (pinfunction "PD13_60") (pintype "bidirectional+no_connect"))
    )
    (net (code "129") (name "unconnected-(U1-PD14-Pad61)") (class "Default")
      (node (ref "U1") (pin "61") (pinfunction "PD14_61") (pintype "bidirectional+no_connect"))
    )
    (net (code "130") (name "unconnected-(U1-PD15-Pad62)") (class "Default")
      (node (ref "U1") (pin "62") (pinfunction "PD15_62") (pintype "bidirectional+no_connect"))
    )
    (net (code "131") (name "unconnected-(U1-PE2-Pad1)") (class "Default")
      (node (ref "U1") (pin "1") (pinfunction "PE2_1") (pintype "bidirectional+no_connect"))
    )
    (net (code "132") (name "unconnected-(U1-PE3-Pad2)") (class "Default")
      (node (ref "U1") (pin "2") (pinfunction "PE3_2") (pintype "bidirectional+no_connect"))
    )
    (net (code "133") (name "unconnected-(U1-PE4-Pad3)") (class "Default")
      (node (ref "U1") (pin "3") (pinfunction "PE4_3") (pintype "bidirectional+no_connect"))
    )
    (net (code "134") (name "unconnected-(U1-PE5-Pad4)") (class "Default")
      (node (ref "U1") (pin "4") (pinfunction "PE5_4") (pintype "bidirectional+no_connect"))
    )
    (net (code "135") (name "unconnected-(U1-PE6-Pad5)") (class "Default")
      (node (ref "U1") (pin "5") (pinfunction "PE6_5") (pintype "bidirectional+no_connect"))
    )
    (net (code "136") (name "unconnected-(U1-PE14-Pad45)") (class "Default")
      (node (ref "U1") (pin "45") (pinfunction "PE14_45") (pintype "bidirectional+no_connect"))
    )
    (net (code "137") (name "unconnected-(U1-PE15-Pad46)") (class "Default")
      (node (ref "U1") (pin "46") (pinfunction "PE15_46") (pintype "bidirectional+no_connect"))
    )
    (net (code "138") (name "unconnected-(U6-NC-Pad1)") (class "Default")
      (node (ref "U6") (pin "1") (pinfunction "NC_1") (pintype "passive+no_connect"))
    )
    (net (code "139") (name "unconnected-(U8-PG-Pad5)") (class "Default")
      (node (ref "U8") (pin "5") (pinfunction "PG_5") (pintype "output+no_connect"))
    )
  )
)
